# SMPS.net
KiCad netlist of a schematic drawn in Altium Designer
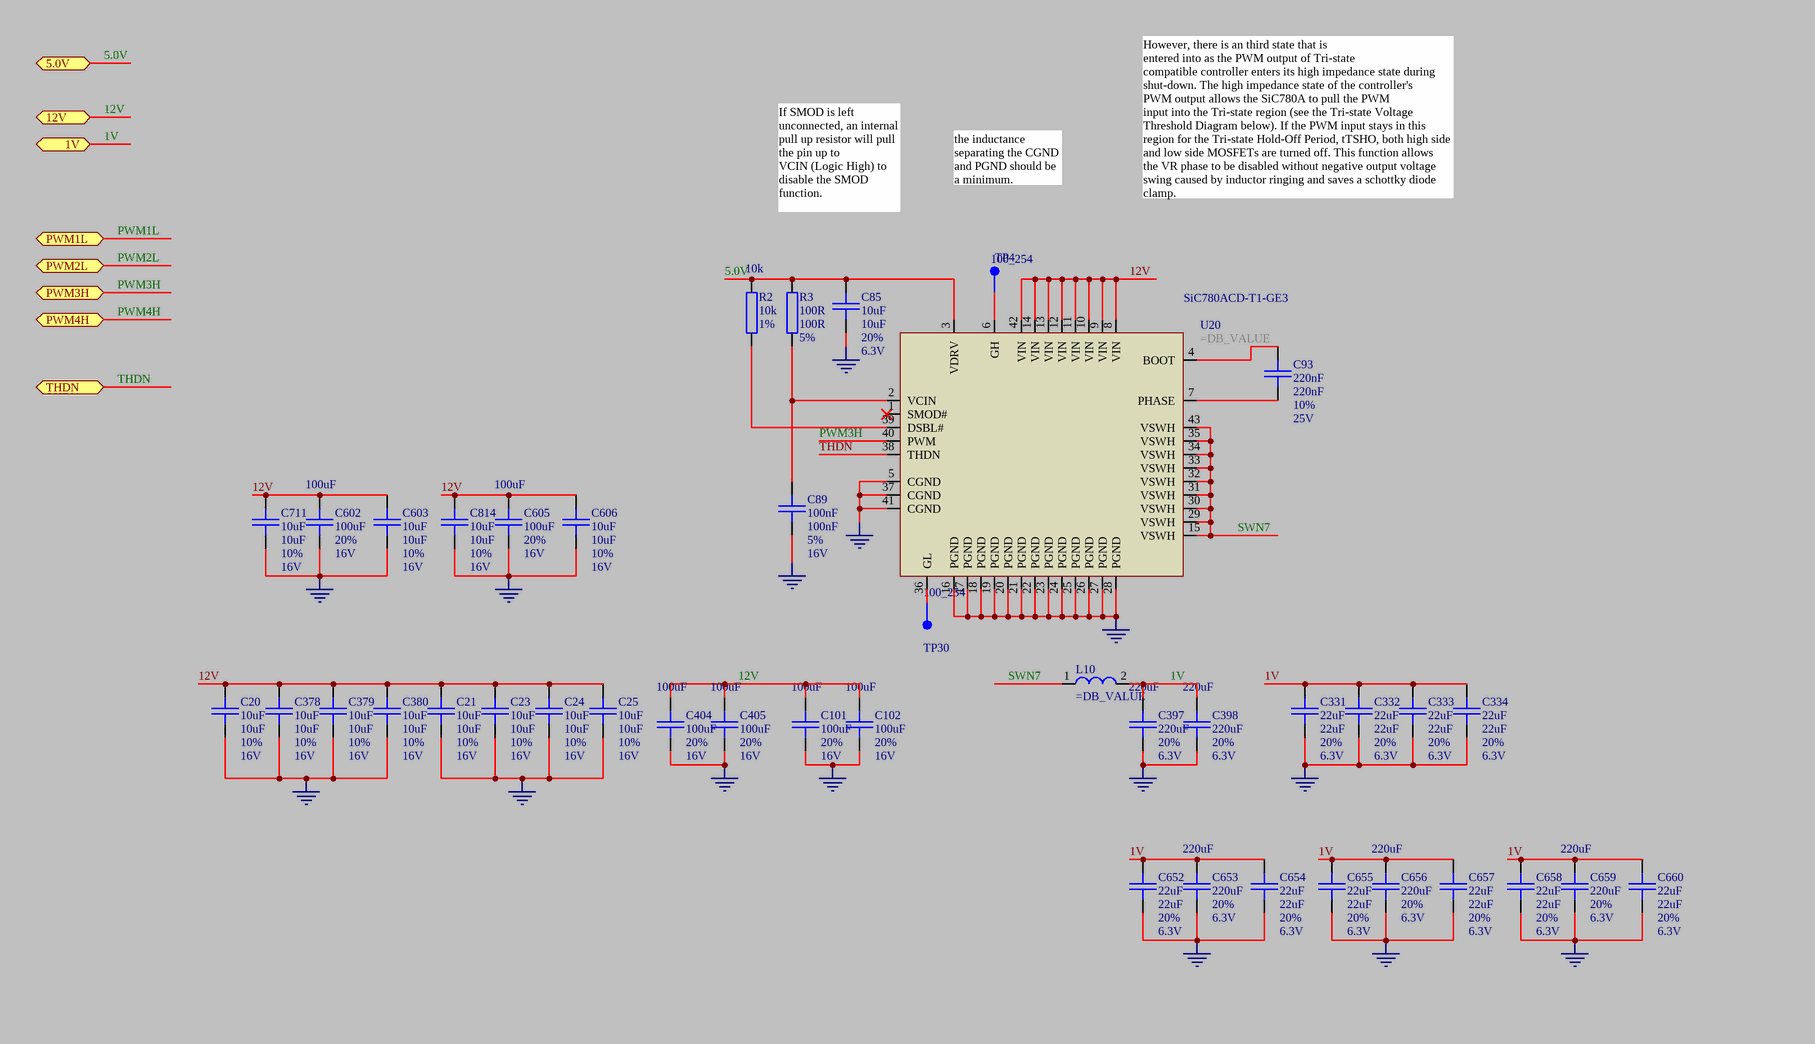
[diagram p0: SMPS.SchDoc, top left]
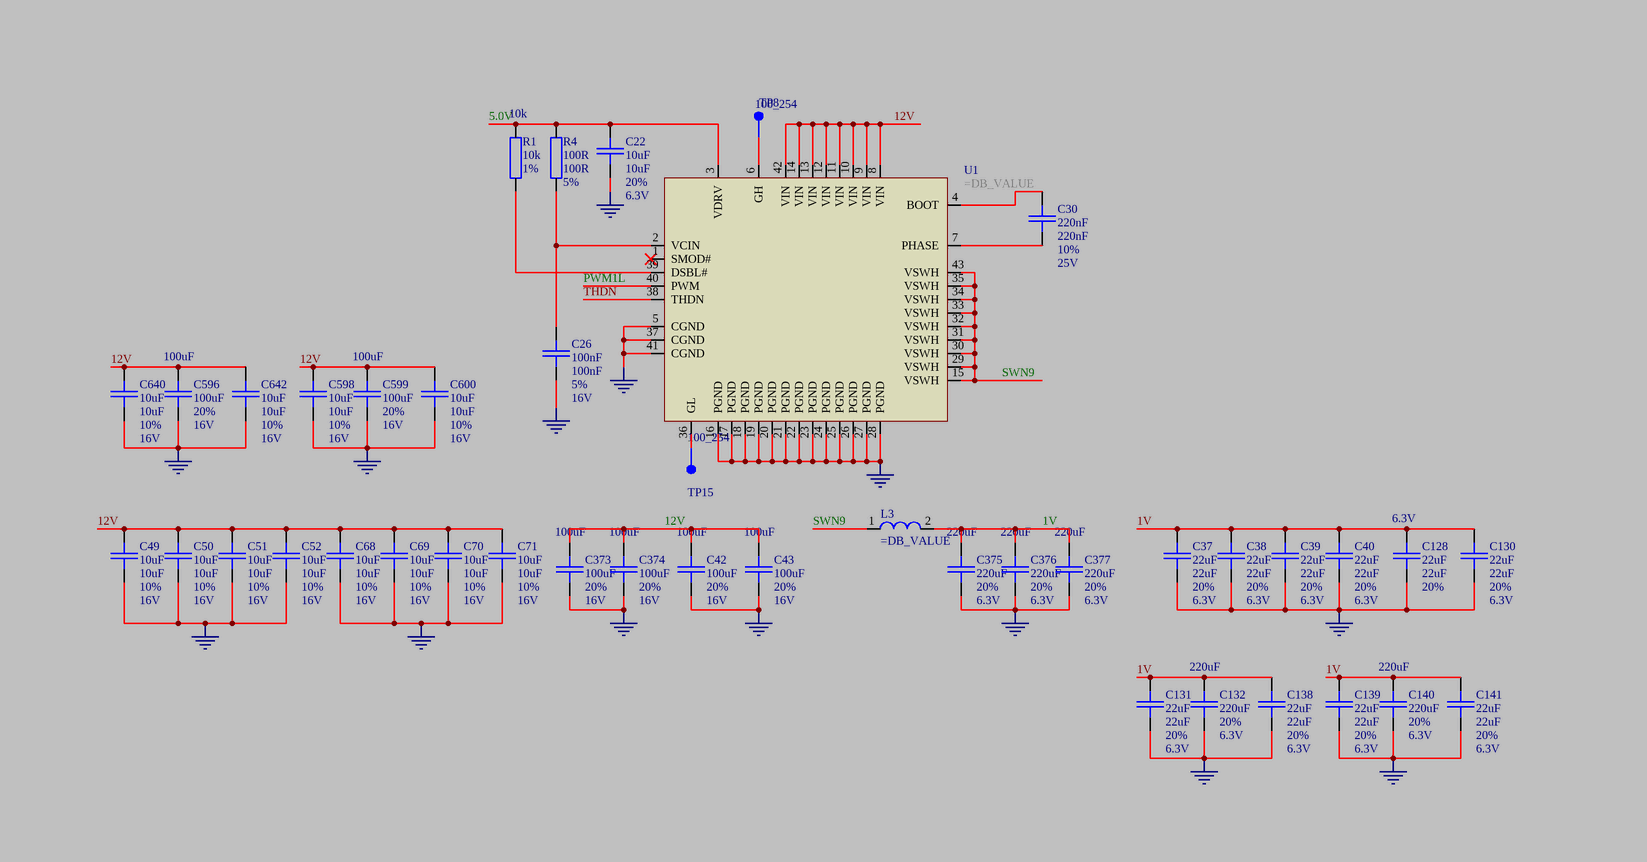
[diagram p1: SMPS.SchDoc, top right]
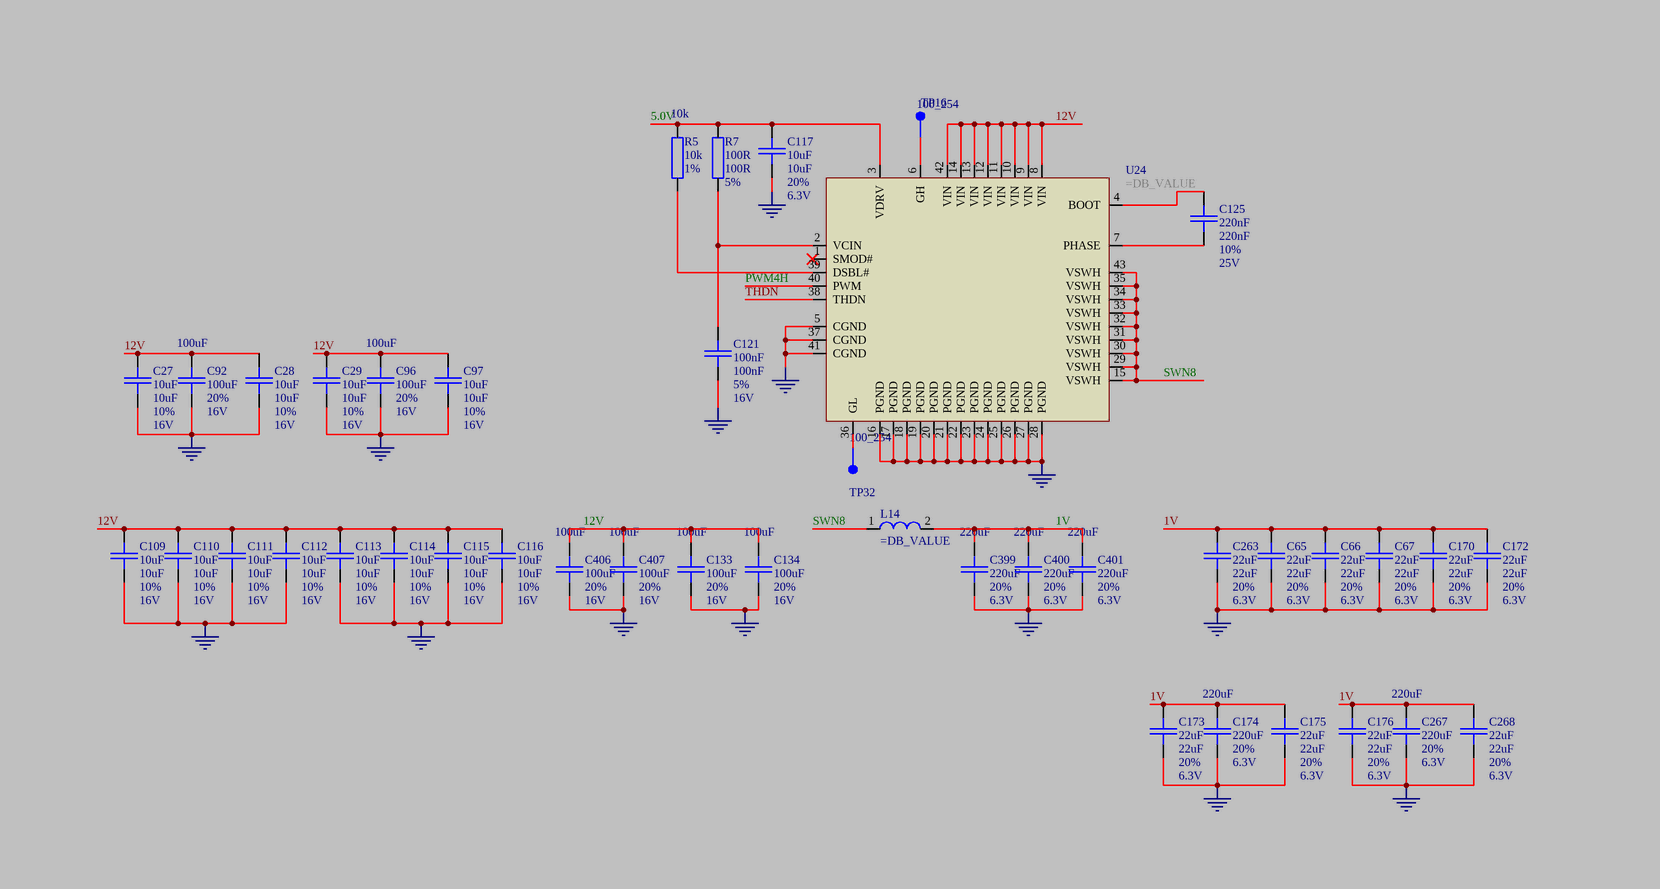
[diagram p2: SMPS.SchDoc, bottom left]
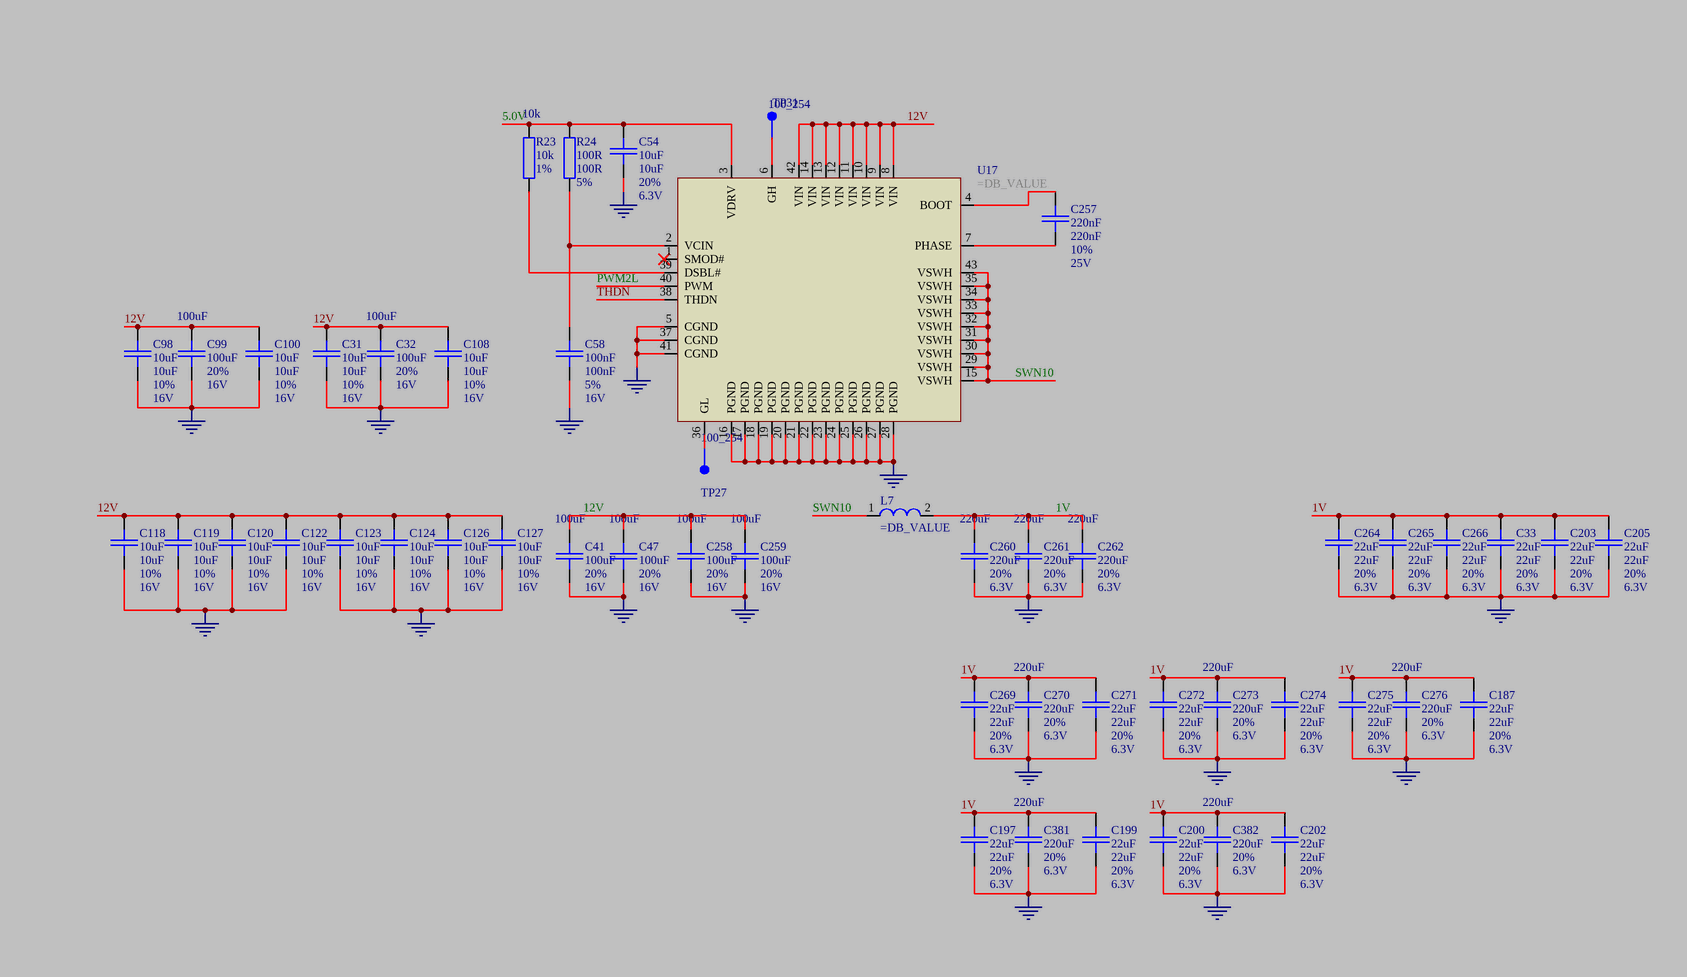
[diagram p3: SMPS.SchDoc, bottom right]

(export (version "E")
  (design (tool "Eeschema 10.0.6"))
  (components
    (comp (ref "C20")
      (value "10uF")
      (footprint "SMD_0805_CAPC2012X145N")
      (fields
        (field (name "DB_PART_NUMBER") "CAP000043636")
        (field (name "DB_VALUE") "10uF")
        (field (name "DB_TOLERANCE") "10%")
        (field (name "DB_VOLTAGE") "16V")
        (field (name "DB_MANUFACTURER_PART") "KEMET    C0805C106K4PAC")
        (field (name "DB_APPROVED_BY") "ISHIDDEN=T")
      )
      (libsource (lib "Database_Libs1") (part "C"))
    )
    (comp (ref "C21")
      (value "10uF")
      (footprint "SMD_0805_CAPC2012X145N")
      (fields
        (field (name "DB_PART_NUMBER") "CAP000043636")
        (field (name "DB_VALUE") "10uF")
        (field (name "DB_TOLERANCE") "10%")
        (field (name "DB_VOLTAGE") "16V")
        (field (name "DB_MANUFACTURER_PART") "KEMET    C0805C106K4PAC")
        (field (name "DB_APPROVED_BY") "ISHIDDEN=T")
      )
      (libsource (lib "Database_Libs1") (part "C"))
    )
    (comp (ref "C22")
      (value "10uF")
      (footprint "SMD_0603_CAPC1608X95N")
      (fields
        (field (name "DB_PART_NUMBER") "CAP000043646")
        (field (name "DB_VALUE") "10uF")
        (field (name "DB_TOLERANCE") "20%")
        (field (name "DB_VOLTAGE") "6.3V")
        (field (name "DB_MANUFACTURER_PART") "KEMET    C0603C106M9PAC")
        (field (name "DB_APPROVED_BY") "ISHIDDEN=T")
      )
      (libsource (lib "Database_Libs1") (part "C"))
    )
    (comp (ref "C23")
      (value "10uF")
      (footprint "SMD_0805_CAPC2012X145N")
      (fields
        (field (name "DB_PART_NUMBER") "CAP000043636")
        (field (name "DB_VALUE") "10uF")
        (field (name "DB_TOLERANCE") "10%")
        (field (name "DB_VOLTAGE") "16V")
        (field (name "DB_MANUFACTURER_PART") "KEMET    C0805C106K4PAC")
        (field (name "DB_APPROVED_BY") "ISHIDDEN=T")
      )
      (libsource (lib "Database_Libs1") (part "C"))
    )
    (comp (ref "C24")
      (value "10uF")
      (footprint "SMD_0805_CAPC2012X145N")
      (fields
        (field (name "DB_PART_NUMBER") "CAP000043636")
        (field (name "DB_VALUE") "10uF")
        (field (name "DB_TOLERANCE") "10%")
        (field (name "DB_VOLTAGE") "16V")
        (field (name "DB_MANUFACTURER_PART") "KEMET    C0805C106K4PAC")
        (field (name "DB_APPROVED_BY") "ISHIDDEN=T")
      )
      (libsource (lib "Database_Libs1") (part "C"))
    )
    (comp (ref "C25")
      (value "10uF")
      (footprint "SMD_0805_CAPC2012X145N")
      (fields
        (field (name "DB_PART_NUMBER") "CAP000043636")
        (field (name "DB_VALUE") "10uF")
        (field (name "DB_TOLERANCE") "10%")
        (field (name "DB_VOLTAGE") "16V")
        (field (name "DB_MANUFACTURER_PART") "KEMET    C0805C106K4PAC")
        (field (name "DB_APPROVED_BY") "ISHIDDEN=T")
      )
      (libsource (lib "Database_Libs1") (part "C"))
    )
    (comp (ref "C26")
      (value "100nF")
      (footprint "SMD_0603_CAPC1608X95N")
      (fields
        (field (name "DB_PART_NUMBER") "CAP000022706")
        (field (name "DB_VALUE") "100nF")
        (field (name "DB_TOLERANCE") "5%")
        (field (name "DB_VOLTAGE") "16V")
        (field (name "DB_MANUFACTURER_PART") "KEMET    C0603F104J4RAC")
        (field (name "DB_APPROVED_BY") "ISHIDDEN=T")
      )
      (libsource (lib "Database_Libs1") (part "C"))
    )
    (comp (ref "C27")
      (value "10uF")
      (footprint "SMD_0805_CAPC2012X145N")
      (fields
        (field (name "DB_PART_NUMBER") "CAP000043636")
        (field (name "DB_VALUE") "10uF")
        (field (name "DB_TOLERANCE") "10%")
        (field (name "DB_VOLTAGE") "16V")
        (field (name "DB_MANUFACTURER_PART") "KEMET    C0805C106K4PAC")
        (field (name "DB_APPROVED_BY") "ISHIDDEN=T")
      )
      (libsource (lib "Database_Libs1") (part "C"))
    )
    (comp (ref "C28")
      (value "10uF")
      (footprint "SMD_0805_CAPC2012X145N")
      (fields
        (field (name "DB_PART_NUMBER") "CAP000043636")
        (field (name "DB_VALUE") "10uF")
        (field (name "DB_TOLERANCE") "10%")
        (field (name "DB_VOLTAGE") "16V")
        (field (name "DB_MANUFACTURER_PART") "KEMET    C0805C106K4PAC")
        (field (name "DB_APPROVED_BY") "ISHIDDEN=T")
      )
      (libsource (lib "Database_Libs1") (part "C"))
    )
    (comp (ref "C29")
      (value "10uF")
      (footprint "SMD_0805_CAPC2012X145N")
      (fields
        (field (name "DB_PART_NUMBER") "CAP000043636")
        (field (name "DB_VALUE") "10uF")
        (field (name "DB_TOLERANCE") "10%")
        (field (name "DB_VOLTAGE") "16V")
        (field (name "DB_MANUFACTURER_PART") "KEMET    C0805C106K4PAC")
        (field (name "DB_APPROVED_BY") "ISHIDDEN=T")
      )
      (libsource (lib "Database_Libs1") (part "C"))
    )
    (comp (ref "C30")
      (value "220nF")
      (footprint "SMD_0603_CAPC1608X95N")
      (fields
        (field (name "DB_PART_NUMBER") "CAP000022968")
        (field (name "DB_VALUE") "220nF")
        (field (name "DB_TOLERANCE") "10%")
        (field (name "DB_VOLTAGE") "25V")
        (field (name "DB_MANUFACTURER_PART") "KEMET    C0603F224K3RAC")
        (field (name "DB_APPROVED_BY") "ISHIDDEN=T")
      )
      (libsource (lib "Database_Libs1") (part "C"))
    )
    (comp (ref "C31")
      (value "10uF")
      (footprint "SMD_0805_CAPC2012X145N")
      (fields
        (field (name "DB_PART_NUMBER") "CAP000043636")
        (field (name "DB_VALUE") "10uF")
        (field (name "DB_TOLERANCE") "10%")
        (field (name "DB_VOLTAGE") "16V")
        (field (name "DB_MANUFACTURER_PART") "KEMET    C0805C106K4PAC")
        (field (name "DB_APPROVED_BY") "ISHIDDEN=T")
      )
      (libsource (lib "Database_Libs1") (part "C"))
    )
    (comp (ref "C32")
      (value "100uF")
      (footprint "SMD_1210_CAPC3225X270N")
      (fields
        (field (name "DB_PART_NUMBER") "TMP-2512")
        (field (name "DB_VALUE") "100uF")
        (field (name "DB_TOLERANCE") "20%")
        (field (name "DB_VOLTAGE") "16V")
        (field (name "DB_MANUFACTURER_PART") "YAGEO    CC1210MRX5R7BB107")
      )
      (libsource (lib "Database_Libs1") (part "C"))
    )
    (comp (ref "C33")
      (value "22uF")
      (footprint "SMD_0805_CAPC2012X145N")
      (fields
        (field (name "DB_PART_NUMBER") "CAP000043686")
        (field (name "DB_VALUE") "22uF")
        (field (name "DB_TOLERANCE") "20%")
        (field (name "DB_VOLTAGE") "6.3V")
        (field (name "DB_MANUFACTURER_PART") "KEMET    C0805C226M9PAC")
        (field (name "DB_APPROVED_BY") "ISHIDDEN=T")
      )
      (libsource (lib "Database_Libs1") (part "C"))
    )
    (comp (ref "C37")
      (value "22uF")
      (footprint "SMD_0805_CAPC2012X145N")
      (fields
        (field (name "DB_PART_NUMBER") "CAP000043686")
        (field (name "DB_VALUE") "22uF")
        (field (name "DB_TOLERANCE") "20%")
        (field (name "DB_VOLTAGE") "6.3V")
        (field (name "DB_MANUFACTURER_PART") "KEMET    C0805C226M9PAC")
        (field (name "DB_APPROVED_BY") "ISHIDDEN=T")
      )
      (libsource (lib "Database_Libs1") (part "C"))
    )
    (comp (ref "C38")
      (value "22uF")
      (footprint "SMD_0805_CAPC2012X145N")
      (fields
        (field (name "DB_PART_NUMBER") "CAP000043686")
        (field (name "DB_VALUE") "22uF")
        (field (name "DB_TOLERANCE") "20%")
        (field (name "DB_VOLTAGE") "6.3V")
        (field (name "DB_MANUFACTURER_PART") "KEMET    C0805C226M9PAC")
        (field (name "DB_APPROVED_BY") "ISHIDDEN=T")
      )
      (libsource (lib "Database_Libs1") (part "C"))
    )
    (comp (ref "C39")
      (value "22uF")
      (footprint "SMD_0805_CAPC2012X145N")
      (fields
        (field (name "DB_PART_NUMBER") "CAP000043686")
        (field (name "DB_VALUE") "22uF")
        (field (name "DB_TOLERANCE") "20%")
        (field (name "DB_VOLTAGE") "6.3V")
        (field (name "DB_MANUFACTURER_PART") "KEMET    C0805C226M9PAC")
        (field (name "DB_APPROVED_BY") "ISHIDDEN=T")
      )
      (libsource (lib "Database_Libs1") (part "C"))
    )
    (comp (ref "C40")
      (value "22uF")
      (footprint "SMD_0805_CAPC2012X145N")
      (fields
        (field (name "DB_PART_NUMBER") "CAP000043686")
        (field (name "DB_VALUE") "22uF")
        (field (name "DB_TOLERANCE") "20%")
        (field (name "DB_VOLTAGE") "6.3V")
        (field (name "DB_MANUFACTURER_PART") "KEMET    C0805C226M9PAC")
        (field (name "DB_APPROVED_BY") "ISHIDDEN=T")
      )
      (libsource (lib "Database_Libs1") (part "C"))
    )
    (comp (ref "C41")
      (value "100uF")
      (footprint "SMD_1210_CAPC3225X270N")
      (fields
        (field (name "DB_PART_NUMBER") "TMP-2512")
        (field (name "DB_VALUE") "100uF")
        (field (name "DB_TOLERANCE") "20%")
        (field (name "DB_VOLTAGE") "16V")
        (field (name "DB_MANUFACTURER_PART") "YAGEO    CC1210MRX5R7BB107")
      )
      (libsource (lib "Database_Libs1") (part "C"))
    )
    (comp (ref "C42")
      (value "100uF")
      (footprint "SMD_1210_CAPC3225X270N")
      (fields
        (field (name "DB_PART_NUMBER") "TMP-2512")
        (field (name "DB_VALUE") "100uF")
        (field (name "DB_TOLERANCE") "20%")
        (field (name "DB_VOLTAGE") "16V")
        (field (name "DB_MANUFACTURER_PART") "YAGEO    CC1210MRX5R7BB107")
      )
      (libsource (lib "Database_Libs1") (part "C"))
    )
    (comp (ref "C43")
      (value "100uF")
      (footprint "SMD_1210_CAPC3225X270N")
      (fields
        (field (name "DB_PART_NUMBER") "TMP-2512")
        (field (name "DB_VALUE") "100uF")
        (field (name "DB_TOLERANCE") "20%")
        (field (name "DB_VOLTAGE") "16V")
        (field (name "DB_MANUFACTURER_PART") "YAGEO    CC1210MRX5R7BB107")
      )
      (libsource (lib "Database_Libs1") (part "C"))
    )
    (comp (ref "C47")
      (value "100uF")
      (footprint "SMD_1210_CAPC3225X270N")
      (fields
        (field (name "DB_PART_NUMBER") "TMP-2512")
        (field (name "DB_VALUE") "100uF")
        (field (name "DB_TOLERANCE") "20%")
        (field (name "DB_VOLTAGE") "16V")
        (field (name "DB_MANUFACTURER_PART") "YAGEO    CC1210MRX5R7BB107")
      )
      (libsource (lib "Database_Libs1") (part "C"))
    )
    (comp (ref "C49")
      (value "10uF")
      (footprint "SMD_0805_CAPC2012X145N")
      (fields
        (field (name "DB_PART_NUMBER") "CAP000043636")
        (field (name "DB_VALUE") "10uF")
        (field (name "DB_TOLERANCE") "10%")
        (field (name "DB_VOLTAGE") "16V")
        (field (name "DB_MANUFACTURER_PART") "KEMET    C0805C106K4PAC")
        (field (name "DB_APPROVED_BY") "ISHIDDEN=T")
      )
      (libsource (lib "Database_Libs1") (part "C"))
    )
    (comp (ref "C50")
      (value "10uF")
      (footprint "SMD_0805_CAPC2012X145N")
      (fields
        (field (name "DB_PART_NUMBER") "CAP000043636")
        (field (name "DB_VALUE") "10uF")
        (field (name "DB_TOLERANCE") "10%")
        (field (name "DB_VOLTAGE") "16V")
        (field (name "DB_MANUFACTURER_PART") "KEMET    C0805C106K4PAC")
        (field (name "DB_APPROVED_BY") "ISHIDDEN=T")
      )
      (libsource (lib "Database_Libs1") (part "C"))
    )
    (comp (ref "C51")
      (value "10uF")
      (footprint "SMD_0805_CAPC2012X145N")
      (fields
        (field (name "DB_PART_NUMBER") "CAP000043636")
        (field (name "DB_VALUE") "10uF")
        (field (name "DB_TOLERANCE") "10%")
        (field (name "DB_VOLTAGE") "16V")
        (field (name "DB_MANUFACTURER_PART") "KEMET    C0805C106K4PAC")
        (field (name "DB_APPROVED_BY") "ISHIDDEN=T")
      )
      (libsource (lib "Database_Libs1") (part "C"))
    )
    (comp (ref "C52")
      (value "10uF")
      (footprint "SMD_0805_CAPC2012X145N")
      (fields
        (field (name "DB_PART_NUMBER") "CAP000043636")
        (field (name "DB_VALUE") "10uF")
        (field (name "DB_TOLERANCE") "10%")
        (field (name "DB_VOLTAGE") "16V")
        (field (name "DB_MANUFACTURER_PART") "KEMET    C0805C106K4PAC")
        (field (name "DB_APPROVED_BY") "ISHIDDEN=T")
      )
      (libsource (lib "Database_Libs1") (part "C"))
    )
    (comp (ref "C54")
      (value "10uF")
      (footprint "SMD_0603_CAPC1608X95N")
      (fields
        (field (name "DB_PART_NUMBER") "CAP000043646")
        (field (name "DB_VALUE") "10uF")
        (field (name "DB_TOLERANCE") "20%")
        (field (name "DB_VOLTAGE") "6.3V")
        (field (name "DB_MANUFACTURER_PART") "KEMET    C0603C106M9PAC")
        (field (name "DB_APPROVED_BY") "ISHIDDEN=T")
      )
      (libsource (lib "Database_Libs1") (part "C"))
    )
    (comp (ref "C58")
      (value "100nF")
      (footprint "SMD_0603_CAPC1608X95N")
      (fields
        (field (name "DB_PART_NUMBER") "CAP000022706")
        (field (name "DB_VALUE") "100nF")
        (field (name "DB_TOLERANCE") "5%")
        (field (name "DB_VOLTAGE") "16V")
        (field (name "DB_MANUFACTURER_PART") "KEMET    C0603F104J4RAC")
        (field (name "DB_APPROVED_BY") "ISHIDDEN=T")
      )
      (libsource (lib "Database_Libs1") (part "C"))
    )
    (comp (ref "C65")
      (value "22uF")
      (footprint "SMD_0805_CAPC2012X145N")
      (fields
        (field (name "DB_PART_NUMBER") "CAP000043686")
        (field (name "DB_VALUE") "22uF")
        (field (name "DB_TOLERANCE") "20%")
        (field (name "DB_VOLTAGE") "6.3V")
        (field (name "DB_MANUFACTURER_PART") "KEMET    C0805C226M9PAC")
        (field (name "DB_APPROVED_BY") "ISHIDDEN=T")
      )
      (libsource (lib "Database_Libs1") (part "C"))
    )
    (comp (ref "C66")
      (value "22uF")
      (footprint "SMD_0805_CAPC2012X145N")
      (fields
        (field (name "DB_PART_NUMBER") "CAP000043686")
        (field (name "DB_VALUE") "22uF")
        (field (name "DB_TOLERANCE") "20%")
        (field (name "DB_VOLTAGE") "6.3V")
        (field (name "DB_MANUFACTURER_PART") "KEMET    C0805C226M9PAC")
        (field (name "DB_APPROVED_BY") "ISHIDDEN=T")
      )
      (libsource (lib "Database_Libs1") (part "C"))
    )
    (comp (ref "C67")
      (value "22uF")
      (footprint "SMD_0805_CAPC2012X145N")
      (fields
        (field (name "DB_PART_NUMBER") "CAP000043686")
        (field (name "DB_VALUE") "22uF")
        (field (name "DB_TOLERANCE") "20%")
        (field (name "DB_VOLTAGE") "6.3V")
        (field (name "DB_MANUFACTURER_PART") "KEMET    C0805C226M9PAC")
        (field (name "DB_APPROVED_BY") "ISHIDDEN=T")
      )
      (libsource (lib "Database_Libs1") (part "C"))
    )
    (comp (ref "C68")
      (value "10uF")
      (footprint "SMD_0805_CAPC2012X145N")
      (fields
        (field (name "DB_PART_NUMBER") "CAP000043636")
        (field (name "DB_VALUE") "10uF")
        (field (name "DB_TOLERANCE") "10%")
        (field (name "DB_VOLTAGE") "16V")
        (field (name "DB_MANUFACTURER_PART") "KEMET    C0805C106K4PAC")
        (field (name "DB_APPROVED_BY") "ISHIDDEN=T")
      )
      (libsource (lib "Database_Libs1") (part "C"))
    )
    (comp (ref "C69")
      (value "10uF")
      (footprint "SMD_0805_CAPC2012X145N")
      (fields
        (field (name "DB_PART_NUMBER") "CAP000043636")
        (field (name "DB_VALUE") "10uF")
        (field (name "DB_TOLERANCE") "10%")
        (field (name "DB_VOLTAGE") "16V")
        (field (name "DB_MANUFACTURER_PART") "KEMET    C0805C106K4PAC")
        (field (name "DB_APPROVED_BY") "ISHIDDEN=T")
      )
      (libsource (lib "Database_Libs1") (part "C"))
    )
    (comp (ref "C70")
      (value "10uF")
      (footprint "SMD_0805_CAPC2012X145N")
      (fields
        (field (name "DB_PART_NUMBER") "CAP000043636")
        (field (name "DB_VALUE") "10uF")
        (field (name "DB_TOLERANCE") "10%")
        (field (name "DB_VOLTAGE") "16V")
        (field (name "DB_MANUFACTURER_PART") "KEMET    C0805C106K4PAC")
        (field (name "DB_APPROVED_BY") "ISHIDDEN=T")
      )
      (libsource (lib "Database_Libs1") (part "C"))
    )
    (comp (ref "C71")
      (value "10uF")
      (footprint "SMD_0805_CAPC2012X145N")
      (fields
        (field (name "DB_PART_NUMBER") "CAP000043636")
        (field (name "DB_VALUE") "10uF")
        (field (name "DB_TOLERANCE") "10%")
        (field (name "DB_VOLTAGE") "16V")
        (field (name "DB_MANUFACTURER_PART") "KEMET    C0805C106K4PAC")
        (field (name "DB_APPROVED_BY") "ISHIDDEN=T")
      )
      (libsource (lib "Database_Libs1") (part "C"))
    )
    (comp (ref "C85")
      (value "10uF")
      (footprint "SMD_0603_CAPC1608X95N")
      (fields
        (field (name "DB_PART_NUMBER") "CAP000043646")
        (field (name "DB_VALUE") "10uF")
        (field (name "DB_TOLERANCE") "20%")
        (field (name "DB_VOLTAGE") "6.3V")
        (field (name "DB_MANUFACTURER_PART") "KEMET    C0603C106M9PAC")
        (field (name "DB_APPROVED_BY") "ISHIDDEN=T")
      )
      (libsource (lib "Database_Libs1") (part "C"))
    )
    (comp (ref "C89")
      (value "100nF")
      (footprint "SMD_0603_CAPC1608X95N")
      (fields
        (field (name "DB_PART_NUMBER") "CAP000022706")
        (field (name "DB_VALUE") "100nF")
        (field (name "DB_TOLERANCE") "5%")
        (field (name "DB_VOLTAGE") "16V")
        (field (name "DB_MANUFACTURER_PART") "KEMET    C0603F104J4RAC")
        (field (name "DB_APPROVED_BY") "ISHIDDEN=T")
      )
      (libsource (lib "Database_Libs1") (part "C"))
    )
    (comp (ref "C92")
      (value "100uF")
      (footprint "SMD_1210_CAPC3225X270N")
      (fields
        (field (name "DB_PART_NUMBER") "TMP-2512")
        (field (name "DB_VALUE") "100uF")
        (field (name "DB_TOLERANCE") "20%")
        (field (name "DB_VOLTAGE") "16V")
        (field (name "DB_MANUFACTURER_PART") "YAGEO    CC1210MRX5R7BB107")
      )
      (libsource (lib "Database_Libs1") (part "C"))
    )
    (comp (ref "C93")
      (value "220nF")
      (footprint "SMD_0603_CAPC1608X95N")
      (fields
        (field (name "DB_PART_NUMBER") "CAP000022968")
        (field (name "DB_VALUE") "220nF")
        (field (name "DB_TOLERANCE") "10%")
        (field (name "DB_VOLTAGE") "25V")
        (field (name "DB_MANUFACTURER_PART") "KEMET    C0603F224K3RAC")
        (field (name "DB_APPROVED_BY") "ISHIDDEN=T")
      )
      (libsource (lib "Database_Libs1") (part "C"))
    )
    (comp (ref "C96")
      (value "100uF")
      (footprint "SMD_1210_CAPC3225X270N")
      (fields
        (field (name "DB_PART_NUMBER") "TMP-2512")
        (field (name "DB_VALUE") "100uF")
        (field (name "DB_TOLERANCE") "20%")
        (field (name "DB_VOLTAGE") "16V")
        (field (name "DB_MANUFACTURER_PART") "YAGEO    CC1210MRX5R7BB107")
      )
      (libsource (lib "Database_Libs1") (part "C"))
    )
    (comp (ref "C97")
      (value "10uF")
      (footprint "SMD_0805_CAPC2012X145N")
      (fields
        (field (name "DB_PART_NUMBER") "CAP000043636")
        (field (name "DB_VALUE") "10uF")
        (field (name "DB_TOLERANCE") "10%")
        (field (name "DB_VOLTAGE") "16V")
        (field (name "DB_MANUFACTURER_PART") "KEMET    C0805C106K4PAC")
        (field (name "DB_APPROVED_BY") "ISHIDDEN=T")
      )
      (libsource (lib "Database_Libs1") (part "C"))
    )
    (comp (ref "C98")
      (value "10uF")
      (footprint "SMD_0805_CAPC2012X145N")
      (fields
        (field (name "DB_PART_NUMBER") "CAP000043636")
        (field (name "DB_VALUE") "10uF")
        (field (name "DB_TOLERANCE") "10%")
        (field (name "DB_VOLTAGE") "16V")
        (field (name "DB_MANUFACTURER_PART") "KEMET    C0805C106K4PAC")
        (field (name "DB_APPROVED_BY") "ISHIDDEN=T")
      )
      (libsource (lib "Database_Libs1") (part "C"))
    )
    (comp (ref "C99")
      (value "100uF")
      (footprint "SMD_1210_CAPC3225X270N")
      (fields
        (field (name "DB_PART_NUMBER") "TMP-2512")
        (field (name "DB_VALUE") "100uF")
        (field (name "DB_TOLERANCE") "20%")
        (field (name "DB_VOLTAGE") "16V")
        (field (name "DB_MANUFACTURER_PART") "YAGEO    CC1210MRX5R7BB107")
      )
      (libsource (lib "Database_Libs1") (part "C"))
    )
    (comp (ref "C100")
      (value "10uF")
      (footprint "SMD_0805_CAPC2012X145N")
      (fields
        (field (name "DB_PART_NUMBER") "CAP000043636")
        (field (name "DB_VALUE") "10uF")
        (field (name "DB_TOLERANCE") "10%")
        (field (name "DB_VOLTAGE") "16V")
        (field (name "DB_MANUFACTURER_PART") "KEMET    C0805C106K4PAC")
        (field (name "DB_APPROVED_BY") "ISHIDDEN=T")
      )
      (libsource (lib "Database_Libs1") (part "C"))
    )
    (comp (ref "C101")
      (value "100uF")
      (footprint "SMD_1210_CAPC3225X270N")
      (fields
        (field (name "DB_PART_NUMBER") "TMP-2512")
        (field (name "DB_VALUE") "100uF")
        (field (name "DB_TOLERANCE") "20%")
        (field (name "DB_VOLTAGE") "16V")
        (field (name "DB_MANUFACTURER_PART") "YAGEO    CC1210MRX5R7BB107")
      )
      (libsource (lib "Database_Libs1") (part "C"))
    )
    (comp (ref "C102")
      (value "100uF")
      (footprint "SMD_1210_CAPC3225X270N")
      (fields
        (field (name "DB_PART_NUMBER") "TMP-2512")
        (field (name "DB_VALUE") "100uF")
        (field (name "DB_TOLERANCE") "20%")
        (field (name "DB_VOLTAGE") "16V")
        (field (name "DB_MANUFACTURER_PART") "YAGEO    CC1210MRX5R7BB107")
      )
      (libsource (lib "Database_Libs1") (part "C"))
    )
    (comp (ref "C108")
      (value "10uF")
      (footprint "SMD_0805_CAPC2012X145N")
      (fields
        (field (name "DB_PART_NUMBER") "CAP000043636")
        (field (name "DB_VALUE") "10uF")
        (field (name "DB_TOLERANCE") "10%")
        (field (name "DB_VOLTAGE") "16V")
        (field (name "DB_MANUFACTURER_PART") "KEMET    C0805C106K4PAC")
        (field (name "DB_APPROVED_BY") "ISHIDDEN=T")
      )
      (libsource (lib "Database_Libs1") (part "C"))
    )
    (comp (ref "C109")
      (value "10uF")
      (footprint "SMD_0805_CAPC2012X145N")
      (fields
        (field (name "DB_PART_NUMBER") "CAP000043636")
        (field (name "DB_VALUE") "10uF")
        (field (name "DB_TOLERANCE") "10%")
        (field (name "DB_VOLTAGE") "16V")
        (field (name "DB_MANUFACTURER_PART") "KEMET    C0805C106K4PAC")
        (field (name "DB_APPROVED_BY") "ISHIDDEN=T")
      )
      (libsource (lib "Database_Libs1") (part "C"))
    )
    (comp (ref "C110")
      (value "10uF")
      (footprint "SMD_0805_CAPC2012X145N")
      (fields
        (field (name "DB_PART_NUMBER") "CAP000043636")
        (field (name "DB_VALUE") "10uF")
        (field (name "DB_TOLERANCE") "10%")
        (field (name "DB_VOLTAGE") "16V")
        (field (name "DB_MANUFACTURER_PART") "KEMET    C0805C106K4PAC")
        (field (name "DB_APPROVED_BY") "ISHIDDEN=T")
      )
      (libsource (lib "Database_Libs1") (part "C"))
    )
    (comp (ref "C111")
      (value "10uF")
      (footprint "SMD_0805_CAPC2012X145N")
      (fields
        (field (name "DB_PART_NUMBER") "CAP000043636")
        (field (name "DB_VALUE") "10uF")
        (field (name "DB_TOLERANCE") "10%")
        (field (name "DB_VOLTAGE") "16V")
        (field (name "DB_MANUFACTURER_PART") "KEMET    C0805C106K4PAC")
        (field (name "DB_APPROVED_BY") "ISHIDDEN=T")
      )
      (libsource (lib "Database_Libs1") (part "C"))
    )
    (comp (ref "C112")
      (value "10uF")
      (footprint "SMD_0805_CAPC2012X145N")
      (fields
        (field (name "DB_PART_NUMBER") "CAP000043636")
        (field (name "DB_VALUE") "10uF")
        (field (name "DB_TOLERANCE") "10%")
        (field (name "DB_VOLTAGE") "16V")
        (field (name "DB_MANUFACTURER_PART") "KEMET    C0805C106K4PAC")
        (field (name "DB_APPROVED_BY") "ISHIDDEN=T")
      )
      (libsource (lib "Database_Libs1") (part "C"))
    )
    (comp (ref "C113")
      (value "10uF")
      (footprint "SMD_0805_CAPC2012X145N")
      (fields
        (field (name "DB_PART_NUMBER") "CAP000043636")
        (field (name "DB_VALUE") "10uF")
        (field (name "DB_TOLERANCE") "10%")
        (field (name "DB_VOLTAGE") "16V")
        (field (name "DB_MANUFACTURER_PART") "KEMET    C0805C106K4PAC")
        (field (name "DB_APPROVED_BY") "ISHIDDEN=T")
      )
      (libsource (lib "Database_Libs1") (part "C"))
    )
    (comp (ref "C114")
      (value "10uF")
      (footprint "SMD_0805_CAPC2012X145N")
      (fields
        (field (name "DB_PART_NUMBER") "CAP000043636")
        (field (name "DB_VALUE") "10uF")
        (field (name "DB_TOLERANCE") "10%")
        (field (name "DB_VOLTAGE") "16V")
        (field (name "DB_MANUFACTURER_PART") "KEMET    C0805C106K4PAC")
        (field (name "DB_APPROVED_BY") "ISHIDDEN=T")
      )
      (libsource (lib "Database_Libs1") (part "C"))
    )
    (comp (ref "C115")
      (value "10uF")
      (footprint "SMD_0805_CAPC2012X145N")
      (fields
        (field (name "DB_PART_NUMBER") "CAP000043636")
        (field (name "DB_VALUE") "10uF")
        (field (name "DB_TOLERANCE") "10%")
        (field (name "DB_VOLTAGE") "16V")
        (field (name "DB_MANUFACTURER_PART") "KEMET    C0805C106K4PAC")
        (field (name "DB_APPROVED_BY") "ISHIDDEN=T")
      )
      (libsource (lib "Database_Libs1") (part "C"))
    )
    (comp (ref "C116")
      (value "10uF")
      (footprint "SMD_0805_CAPC2012X145N")
      (fields
        (field (name "DB_PART_NUMBER") "CAP000043636")
        (field (name "DB_VALUE") "10uF")
        (field (name "DB_TOLERANCE") "10%")
        (field (name "DB_VOLTAGE") "16V")
        (field (name "DB_MANUFACTURER_PART") "KEMET    C0805C106K4PAC")
        (field (name "DB_APPROVED_BY") "ISHIDDEN=T")
      )
      (libsource (lib "Database_Libs1") (part "C"))
    )
    (comp (ref "C117")
      (value "10uF")
      (footprint "SMD_0603_CAPC1608X95N")
      (fields
        (field (name "DB_PART_NUMBER") "CAP000043646")
        (field (name "DB_VALUE") "10uF")
        (field (name "DB_TOLERANCE") "20%")
        (field (name "DB_VOLTAGE") "6.3V")
        (field (name "DB_MANUFACTURER_PART") "KEMET    C0603C106M9PAC")
        (field (name "DB_APPROVED_BY") "ISHIDDEN=T")
      )
      (libsource (lib "Database_Libs1") (part "C"))
    )
    (comp (ref "C118")
      (value "10uF")
      (footprint "SMD_0805_CAPC2012X145N")
      (fields
        (field (name "DB_PART_NUMBER") "CAP000043636")
        (field (name "DB_VALUE") "10uF")
        (field (name "DB_TOLERANCE") "10%")
        (field (name "DB_VOLTAGE") "16V")
        (field (name "DB_MANUFACTURER_PART") "KEMET    C0805C106K4PAC")
        (field (name "DB_APPROVED_BY") "ISHIDDEN=T")
      )
      (libsource (lib "Database_Libs1") (part "C"))
    )
    (comp (ref "C119")
      (value "10uF")
      (footprint "SMD_0805_CAPC2012X145N")
      (fields
        (field (name "DB_PART_NUMBER") "CAP000043636")
        (field (name "DB_VALUE") "10uF")
        (field (name "DB_TOLERANCE") "10%")
        (field (name "DB_VOLTAGE") "16V")
        (field (name "DB_MANUFACTURER_PART") "KEMET    C0805C106K4PAC")
        (field (name "DB_APPROVED_BY") "ISHIDDEN=T")
      )
      (libsource (lib "Database_Libs1") (part "C"))
    )
    (comp (ref "C120")
      (value "10uF")
      (footprint "SMD_0805_CAPC2012X145N")
      (fields
        (field (name "DB_PART_NUMBER") "CAP000043636")
        (field (name "DB_VALUE") "10uF")
        (field (name "DB_TOLERANCE") "10%")
        (field (name "DB_VOLTAGE") "16V")
        (field (name "DB_MANUFACTURER_PART") "KEMET    C0805C106K4PAC")
        (field (name "DB_APPROVED_BY") "ISHIDDEN=T")
      )
      (libsource (lib "Database_Libs1") (part "C"))
    )
    (comp (ref "C121")
      (value "100nF")
      (footprint "SMD_0603_CAPC1608X95N")
      (fields
        (field (name "DB_PART_NUMBER") "CAP000022706")
        (field (name "DB_VALUE") "100nF")
        (field (name "DB_TOLERANCE") "5%")
        (field (name "DB_VOLTAGE") "16V")
        (field (name "DB_MANUFACTURER_PART") "KEMET    C0603F104J4RAC")
        (field (name "DB_APPROVED_BY") "ISHIDDEN=T")
      )
      (libsource (lib "Database_Libs1") (part "C"))
    )
    (comp (ref "C122")
      (value "10uF")
      (footprint "SMD_0805_CAPC2012X145N")
      (fields
        (field (name "DB_PART_NUMBER") "CAP000043636")
        (field (name "DB_VALUE") "10uF")
        (field (name "DB_TOLERANCE") "10%")
        (field (name "DB_VOLTAGE") "16V")
        (field (name "DB_MANUFACTURER_PART") "KEMET    C0805C106K4PAC")
        (field (name "DB_APPROVED_BY") "ISHIDDEN=T")
      )
      (libsource (lib "Database_Libs1") (part "C"))
    )
    (comp (ref "C123")
      (value "10uF")
      (footprint "SMD_0805_CAPC2012X145N")
      (fields
        (field (name "DB_PART_NUMBER") "CAP000043636")
        (field (name "DB_VALUE") "10uF")
        (field (name "DB_TOLERANCE") "10%")
        (field (name "DB_VOLTAGE") "16V")
        (field (name "DB_MANUFACTURER_PART") "KEMET    C0805C106K4PAC")
        (field (name "DB_APPROVED_BY") "ISHIDDEN=T")
      )
      (libsource (lib "Database_Libs1") (part "C"))
    )
    (comp (ref "C124")
      (value "10uF")
      (footprint "SMD_0805_CAPC2012X145N")
      (fields
        (field (name "DB_PART_NUMBER") "CAP000043636")
        (field (name "DB_VALUE") "10uF")
        (field (name "DB_TOLERANCE") "10%")
        (field (name "DB_VOLTAGE") "16V")
        (field (name "DB_MANUFACTURER_PART") "KEMET    C0805C106K4PAC")
        (field (name "DB_APPROVED_BY") "ISHIDDEN=T")
      )
      (libsource (lib "Database_Libs1") (part "C"))
    )
    (comp (ref "C125")
      (value "220nF")
      (footprint "SMD_0603_CAPC1608X95N")
      (fields
        (field (name "DB_PART_NUMBER") "CAP000022968")
        (field (name "DB_VALUE") "220nF")
        (field (name "DB_TOLERANCE") "10%")
        (field (name "DB_VOLTAGE") "25V")
        (field (name "DB_MANUFACTURER_PART") "KEMET    C0603F224K3RAC")
        (field (name "DB_APPROVED_BY") "ISHIDDEN=T")
      )
      (libsource (lib "Database_Libs1") (part "C"))
    )
    (comp (ref "C126")
      (value "10uF")
      (footprint "SMD_0805_CAPC2012X145N")
      (fields
        (field (name "DB_PART_NUMBER") "CAP000043636")
        (field (name "DB_VALUE") "10uF")
        (field (name "DB_TOLERANCE") "10%")
        (field (name "DB_VOLTAGE") "16V")
        (field (name "DB_MANUFACTURER_PART") "KEMET    C0805C106K4PAC")
        (field (name "DB_APPROVED_BY") "ISHIDDEN=T")
      )
      (libsource (lib "Database_Libs1") (part "C"))
    )
    (comp (ref "C127")
      (value "10uF")
      (footprint "SMD_0805_CAPC2012X145N")
      (fields
        (field (name "DB_PART_NUMBER") "CAP000043636")
        (field (name "DB_VALUE") "10uF")
        (field (name "DB_TOLERANCE") "10%")
        (field (name "DB_VOLTAGE") "16V")
        (field (name "DB_MANUFACTURER_PART") "KEMET    C0805C106K4PAC")
        (field (name "DB_APPROVED_BY") "ISHIDDEN=T")
      )
      (libsource (lib "Database_Libs1") (part "C"))
    )
    (comp (ref "C128")
      (value "22uF")
      (footprint "SMD_0805_CAPC2012X145N")
      (fields
        (field (name "DB_PART_NUMBER") "CAP000043686")
        (field (name "DB_VALUE") "22uF")
        (field (name "DB_TOLERANCE") "20%")
        (field (name "DB_MANUFACTURER_PART") "KEMET    C0805C226M9PAC")
        (field (name "DB_VOLTAGE") "6.3V")
        (field (name "DB_APPROVED_BY") "ISHIDDEN=T")
      )
      (libsource (lib "Database_Libs1") (part "C"))
    )
    (comp (ref "C130")
      (value "22uF")
      (footprint "SMD_0805_CAPC2012X145N")
      (fields
        (field (name "DB_PART_NUMBER") "CAP000043686")
        (field (name "DB_VALUE") "22uF")
        (field (name "DB_TOLERANCE") "20%")
        (field (name "DB_VOLTAGE") "6.3V")
        (field (name "DB_MANUFACTURER_PART") "KEMET    C0805C226M9PAC")
        (field (name "DB_APPROVED_BY") "ISHIDDEN=T")
      )
      (libsource (lib "Database_Libs1") (part "C"))
    )
    (comp (ref "C131")
      (value "22uF")
      (footprint "SMD_0805_CAPC2012X145N")
      (fields
        (field (name "DB_PART_NUMBER") "CAP000043686")
        (field (name "DB_VALUE") "22uF")
        (field (name "DB_TOLERANCE") "20%")
        (field (name "DB_VOLTAGE") "6.3V")
        (field (name "DB_MANUFACTURER_PART") "KEMET    C0805C226M9PAC")
        (field (name "DB_APPROVED_BY") "ISHIDDEN=T")
      )
      (libsource (lib "Database_Libs1") (part "C"))
    )
    (comp (ref "C132")
      (value "220uF")
      (footprint "SMD_1210_CAPC3225X279N")
      (fields
        (field (name "DB_PART_NUMBER") "CAP000047355")
        (field (name "DB_VALUE") "220uF")
        (field (name "DB_TOLERANCE") "20%")
        (field (name "DB_VOLTAGE") "6.3V")
        (field (name "DB_MANUFACTURER_PART") "SAMSUNG    CL32A227MQVNNNE")
        (field (name "DB_APPROVED_BY") "VSN")
      )
      (libsource (lib "Database_Libs1") (part "C"))
    )
    (comp (ref "C133")
      (value "100uF")
      (footprint "SMD_1210_CAPC3225X270N")
      (fields
        (field (name "DB_PART_NUMBER") "TMP-2512")
        (field (name "DB_VALUE") "100uF")
        (field (name "DB_TOLERANCE") "20%")
        (field (name "DB_VOLTAGE") "16V")
        (field (name "DB_MANUFACTURER_PART") "YAGEO    CC1210MRX5R7BB107")
      )
      (libsource (lib "Database_Libs1") (part "C"))
    )
    (comp (ref "C134")
      (value "100uF")
      (footprint "SMD_1210_CAPC3225X270N")
      (fields
        (field (name "DB_PART_NUMBER") "TMP-2512")
        (field (name "DB_VALUE") "100uF")
        (field (name "DB_TOLERANCE") "20%")
        (field (name "DB_VOLTAGE") "16V")
        (field (name "DB_MANUFACTURER_PART") "YAGEO    CC1210MRX5R7BB107")
      )
      (libsource (lib "Database_Libs1") (part "C"))
    )
    (comp (ref "C138")
      (value "22uF")
      (footprint "SMD_0805_CAPC2012X145N")
      (fields
        (field (name "DB_PART_NUMBER") "CAP000043686")
        (field (name "DB_VALUE") "22uF")
        (field (name "DB_TOLERANCE") "20%")
        (field (name "DB_VOLTAGE") "6.3V")
        (field (name "DB_MANUFACTURER_PART") "KEMET    C0805C226M9PAC")
        (field (name "DB_APPROVED_BY") "ISHIDDEN=T")
      )
      (libsource (lib "Database_Libs1") (part "C"))
    )
    (comp (ref "C139")
      (value "22uF")
      (footprint "SMD_0805_CAPC2012X145N")
      (fields
        (field (name "DB_PART_NUMBER") "CAP000043686")
        (field (name "DB_VALUE") "22uF")
        (field (name "DB_TOLERANCE") "20%")
        (field (name "DB_VOLTAGE") "6.3V")
        (field (name "DB_MANUFACTURER_PART") "KEMET    C0805C226M9PAC")
        (field (name "DB_APPROVED_BY") "ISHIDDEN=T")
      )
      (libsource (lib "Database_Libs1") (part "C"))
    )
    (comp (ref "C140")
      (value "220uF")
      (footprint "SMD_1210_CAPC3225X279N")
      (fields
        (field (name "DB_PART_NUMBER") "CAP000047355")
        (field (name "DB_VALUE") "220uF")
        (field (name "DB_TOLERANCE") "20%")
        (field (name "DB_VOLTAGE") "6.3V")
        (field (name "DB_MANUFACTURER_PART") "SAMSUNG    CL32A227MQVNNNE")
        (field (name "DB_APPROVED_BY") "VSN")
      )
      (libsource (lib "Database_Libs1") (part "C"))
    )
    (comp (ref "C141")
      (value "22uF")
      (footprint "SMD_0805_CAPC2012X145N")
      (fields
        (field (name "DB_PART_NUMBER") "CAP000043686")
        (field (name "DB_VALUE") "22uF")
        (field (name "DB_TOLERANCE") "20%")
        (field (name "DB_VOLTAGE") "6.3V")
        (field (name "DB_MANUFACTURER_PART") "KEMET    C0805C226M9PAC")
        (field (name "DB_APPROVED_BY") "ISHIDDEN=T")
      )
      (libsource (lib "Database_Libs1") (part "C"))
    )
    (comp (ref "C170")
      (value "22uF")
      (footprint "SMD_0805_CAPC2012X145N")
      (fields
        (field (name "DB_PART_NUMBER") "CAP000043686")
        (field (name "DB_VALUE") "22uF")
        (field (name "DB_TOLERANCE") "20%")
        (field (name "DB_VOLTAGE") "6.3V")
        (field (name "DB_MANUFACTURER_PART") "KEMET    C0805C226M9PAC")
        (field (name "DB_APPROVED_BY") "ISHIDDEN=T")
      )
      (libsource (lib "Database_Libs1") (part "C"))
    )
    (comp (ref "C172")
      (value "22uF")
      (footprint "SMD_0805_CAPC2012X145N")
      (fields
        (field (name "DB_PART_NUMBER") "CAP000043686")
        (field (name "DB_VALUE") "22uF")
        (field (name "DB_TOLERANCE") "20%")
        (field (name "DB_VOLTAGE") "6.3V")
        (field (name "DB_MANUFACTURER_PART") "KEMET    C0805C226M9PAC")
        (field (name "DB_APPROVED_BY") "ISHIDDEN=T")
      )
      (libsource (lib "Database_Libs1") (part "C"))
    )
    (comp (ref "C173")
      (value "22uF")
      (footprint "SMD_0805_CAPC2012X145N")
      (fields
        (field (name "DB_PART_NUMBER") "CAP000043686")
        (field (name "DB_VALUE") "22uF")
        (field (name "DB_TOLERANCE") "20%")
        (field (name "DB_VOLTAGE") "6.3V")
        (field (name "DB_MANUFACTURER_PART") "KEMET    C0805C226M9PAC")
        (field (name "DB_APPROVED_BY") "ISHIDDEN=T")
      )
      (libsource (lib "Database_Libs1") (part "C"))
    )
    (comp (ref "C174")
      (value "220uF")
      (footprint "SMD_1210_CAPC3225X279N")
      (fields
        (field (name "DB_PART_NUMBER") "CAP000047355")
        (field (name "DB_VALUE") "220uF")
        (field (name "DB_TOLERANCE") "20%")
        (field (name "DB_VOLTAGE") "6.3V")
        (field (name "DB_MANUFACTURER_PART") "SAMSUNG    CL32A227MQVNNNE")
        (field (name "DB_APPROVED_BY") "VSN")
      )
      (libsource (lib "Database_Libs1") (part "C"))
    )
    (comp (ref "C175")
      (value "22uF")
      (footprint "SMD_0805_CAPC2012X145N")
      (fields
        (field (name "DB_PART_NUMBER") "CAP000043686")
        (field (name "DB_VALUE") "22uF")
        (field (name "DB_TOLERANCE") "20%")
        (field (name "DB_VOLTAGE") "6.3V")
        (field (name "DB_MANUFACTURER_PART") "KEMET    C0805C226M9PAC")
        (field (name "DB_APPROVED_BY") "ISHIDDEN=T")
      )
      (libsource (lib "Database_Libs1") (part "C"))
    )
    (comp (ref "C176")
      (value "22uF")
      (footprint "SMD_0805_CAPC2012X145N")
      (fields
        (field (name "DB_PART_NUMBER") "CAP000043686")
        (field (name "DB_VALUE") "22uF")
        (field (name "DB_TOLERANCE") "20%")
        (field (name "DB_VOLTAGE") "6.3V")
        (field (name "DB_MANUFACTURER_PART") "KEMET    C0805C226M9PAC")
        (field (name "DB_APPROVED_BY") "ISHIDDEN=T")
      )
      (libsource (lib "Database_Libs1") (part "C"))
    )
    (comp (ref "C187")
      (value "22uF")
      (footprint "SMD_0805_CAPC2012X145N")
      (fields
        (field (name "DB_PART_NUMBER") "CAP000043686")
        (field (name "DB_VALUE") "22uF")
        (field (name "DB_TOLERANCE") "20%")
        (field (name "DB_VOLTAGE") "6.3V")
        (field (name "DB_MANUFACTURER_PART") "KEMET    C0805C226M9PAC")
        (field (name "DB_APPROVED_BY") "ISHIDDEN=T")
      )
      (libsource (lib "Database_Libs1") (part "C"))
    )
    (comp (ref "C197")
      (value "22uF")
      (footprint "SMD_0805_CAPC2012X145N")
      (fields
        (field (name "DB_PART_NUMBER") "CAP000043686")
        (field (name "DB_VALUE") "22uF")
        (field (name "DB_TOLERANCE") "20%")
        (field (name "DB_VOLTAGE") "6.3V")
        (field (name "DB_MANUFACTURER_PART") "KEMET    C0805C226M9PAC")
        (field (name "DB_APPROVED_BY") "ISHIDDEN=T")
      )
      (libsource (lib "Database_Libs1") (part "C"))
    )
    (comp (ref "C199")
      (value "22uF")
      (footprint "SMD_0805_CAPC2012X145N")
      (fields
        (field (name "DB_PART_NUMBER") "CAP000043686")
        (field (name "DB_VALUE") "22uF")
        (field (name "DB_TOLERANCE") "20%")
        (field (name "DB_VOLTAGE") "6.3V")
        (field (name "DB_MANUFACTURER_PART") "KEMET    C0805C226M9PAC")
        (field (name "DB_APPROVED_BY") "ISHIDDEN=T")
      )
      (libsource (lib "Database_Libs1") (part "C"))
    )
    (comp (ref "C200")
      (value "22uF")
      (footprint "SMD_0805_CAPC2012X145N")
      (fields
        (field (name "DB_PART_NUMBER") "CAP000043686")
        (field (name "DB_VALUE") "22uF")
        (field (name "DB_TOLERANCE") "20%")
        (field (name "DB_VOLTAGE") "6.3V")
        (field (name "DB_MANUFACTURER_PART") "KEMET    C0805C226M9PAC")
        (field (name "DB_APPROVED_BY") "ISHIDDEN=T")
      )
      (libsource (lib "Database_Libs1") (part "C"))
    )
    (comp (ref "C202")
      (value "22uF")
      (footprint "SMD_0805_CAPC2012X145N")
      (fields
        (field (name "DB_PART_NUMBER") "CAP000043686")
        (field (name "DB_VALUE") "22uF")
        (field (name "DB_TOLERANCE") "20%")
        (field (name "DB_VOLTAGE") "6.3V")
        (field (name "DB_MANUFACTURER_PART") "KEMET    C0805C226M9PAC")
        (field (name "DB_APPROVED_BY") "ISHIDDEN=T")
      )
      (libsource (lib "Database_Libs1") (part "C"))
    )
    (comp (ref "C203")
      (value "22uF")
      (footprint "SMD_0805_CAPC2012X145N")
      (fields
        (field (name "DB_PART_NUMBER") "CAP000043686")
        (field (name "DB_VALUE") "22uF")
        (field (name "DB_TOLERANCE") "20%")
        (field (name "DB_VOLTAGE") "6.3V")
        (field (name "DB_MANUFACTURER_PART") "KEMET    C0805C226M9PAC")
        (field (name "DB_APPROVED_BY") "ISHIDDEN=T")
      )
      (libsource (lib "Database_Libs1") (part "C"))
    )
    (comp (ref "C205")
      (value "22uF")
      (footprint "SMD_0805_CAPC2012X145N")
      (fields
        (field (name "DB_PART_NUMBER") "CAP000043686")
        (field (name "DB_VALUE") "22uF")
        (field (name "DB_TOLERANCE") "20%")
        (field (name "DB_VOLTAGE") "6.3V")
        (field (name "DB_MANUFACTURER_PART") "KEMET    C0805C226M9PAC")
        (field (name "DB_APPROVED_BY") "ISHIDDEN=T")
      )
      (libsource (lib "Database_Libs1") (part "C"))
    )
    (comp (ref "C257")
      (value "220nF")
      (footprint "SMD_0603_CAPC1608X95N")
      (fields
        (field (name "DB_PART_NUMBER") "CAP000022968")
        (field (name "DB_VALUE") "220nF")
        (field (name "DB_TOLERANCE") "10%")
        (field (name "DB_VOLTAGE") "25V")
        (field (name "DB_MANUFACTURER_PART") "KEMET    C0603F224K3RAC")
        (field (name "DB_APPROVED_BY") "ISHIDDEN=T")
      )
      (libsource (lib "Database_Libs1") (part "C"))
    )
    (comp (ref "C258")
      (value "100uF")
      (footprint "SMD_1210_CAPC3225X270N")
      (fields
        (field (name "DB_PART_NUMBER") "TMP-2512")
        (field (name "DB_VALUE") "100uF")
        (field (name "DB_TOLERANCE") "20%")
        (field (name "DB_VOLTAGE") "16V")
        (field (name "DB_MANUFACTURER_PART") "YAGEO    CC1210MRX5R7BB107")
      )
      (libsource (lib "Database_Libs1") (part "C"))
    )
    (comp (ref "C259")
      (value "100uF")
      (footprint "SMD_1210_CAPC3225X270N")
      (fields
        (field (name "DB_PART_NUMBER") "TMP-2512")
        (field (name "DB_VALUE") "100uF")
        (field (name "DB_TOLERANCE") "20%")
        (field (name "DB_VOLTAGE") "16V")
        (field (name "DB_MANUFACTURER_PART") "YAGEO    CC1210MRX5R7BB107")
      )
      (libsource (lib "Database_Libs1") (part "C"))
    )
    (comp (ref "C260")
      (value "220uF")
      (footprint "SMD_1210_CAPC3225X279N")
      (fields
        (field (name "DB_PART_NUMBER") "CAP000047355")
        (field (name "DB_VALUE") "220uF")
        (field (name "DB_TOLERANCE") "20%")
        (field (name "DB_VOLTAGE") "6.3V")
        (field (name "DB_MANUFACTURER_PART") "SAMSUNG    CL32A227MQVNNNE")
        (field (name "DB_APPROVED_BY") "VSN")
      )
      (libsource (lib "Database_Libs1") (part "C"))
    )
    (comp (ref "C261")
      (value "220uF")
      (footprint "SMD_1210_CAPC3225X279N")
      (fields
        (field (name "DB_PART_NUMBER") "CAP000047355")
        (field (name "DB_VALUE") "220uF")
        (field (name "DB_TOLERANCE") "20%")
        (field (name "DB_VOLTAGE") "6.3V")
        (field (name "DB_MANUFACTURER_PART") "SAMSUNG    CL32A227MQVNNNE")
        (field (name "DB_APPROVED_BY") "VSN")
      )
      (libsource (lib "Database_Libs1") (part "C"))
    )
    (comp (ref "C262")
      (value "220uF")
      (footprint "SMD_1210_CAPC3225X279N")
      (fields
        (field (name "DB_PART_NUMBER") "CAP000047355")
        (field (name "DB_VALUE") "220uF")
        (field (name "DB_TOLERANCE") "20%")
        (field (name "DB_VOLTAGE") "6.3V")
        (field (name "DB_MANUFACTURER_PART") "SAMSUNG    CL32A227MQVNNNE")
        (field (name "DB_APPROVED_BY") "VSN")
      )
      (libsource (lib "Database_Libs1") (part "C"))
    )
    (comp (ref "C263")
      (value "22uF")
      (footprint "SMD_0805_CAPC2012X145N")
      (fields
        (field (name "DB_PART_NUMBER") "CAP000043686")
        (field (name "DB_VALUE") "22uF")
        (field (name "DB_TOLERANCE") "20%")
        (field (name "DB_VOLTAGE") "6.3V")
        (field (name "DB_MANUFACTURER_PART") "KEMET    C0805C226M9PAC")
        (field (name "DB_APPROVED_BY") "ISHIDDEN=T")
      )
      (libsource (lib "Database_Libs1") (part "C"))
    )
    (comp (ref "C264")
      (value "22uF")
      (footprint "SMD_0805_CAPC2012X145N")
      (fields
        (field (name "DB_PART_NUMBER") "CAP000043686")
        (field (name "DB_VALUE") "22uF")
        (field (name "DB_TOLERANCE") "20%")
        (field (name "DB_VOLTAGE") "6.3V")
        (field (name "DB_MANUFACTURER_PART") "KEMET    C0805C226M9PAC")
        (field (name "DB_APPROVED_BY") "ISHIDDEN=T")
      )
      (libsource (lib "Database_Libs1") (part "C"))
    )
    (comp (ref "C265")
      (value "22uF")
      (footprint "SMD_0805_CAPC2012X145N")
      (fields
        (field (name "DB_PART_NUMBER") "CAP000043686")
        (field (name "DB_VALUE") "22uF")
        (field (name "DB_TOLERANCE") "20%")
        (field (name "DB_VOLTAGE") "6.3V")
        (field (name "DB_MANUFACTURER_PART") "KEMET    C0805C226M9PAC")
        (field (name "DB_APPROVED_BY") "ISHIDDEN=T")
      )
      (libsource (lib "Database_Libs1") (part "C"))
    )
    (comp (ref "C266")
      (value "22uF")
      (footprint "SMD_0805_CAPC2012X145N")
      (fields
        (field (name "DB_PART_NUMBER") "CAP000043686")
        (field (name "DB_VALUE") "22uF")
        (field (name "DB_TOLERANCE") "20%")
        (field (name "DB_VOLTAGE") "6.3V")
        (field (name "DB_MANUFACTURER_PART") "KEMET    C0805C226M9PAC")
        (field (name "DB_APPROVED_BY") "ISHIDDEN=T")
      )
      (libsource (lib "Database_Libs1") (part "C"))
    )
    (comp (ref "C267")
      (value "220uF")
      (footprint "SMD_1210_CAPC3225X279N")
      (fields
        (field (name "DB_PART_NUMBER") "CAP000047355")
        (field (name "DB_VALUE") "220uF")
        (field (name "DB_TOLERANCE") "20%")
        (field (name "DB_VOLTAGE") "6.3V")
        (field (name "DB_MANUFACTURER_PART") "SAMSUNG    CL32A227MQVNNNE")
        (field (name "DB_APPROVED_BY") "VSN")
      )
      (libsource (lib "Database_Libs1") (part "C"))
    )
    (comp (ref "C268")
      (value "22uF")
      (footprint "SMD_0805_CAPC2012X145N")
      (fields
        (field (name "DB_PART_NUMBER") "CAP000043686")
        (field (name "DB_VALUE") "22uF")
        (field (name "DB_TOLERANCE") "20%")
        (field (name "DB_VOLTAGE") "6.3V")
        (field (name "DB_MANUFACTURER_PART") "KEMET    C0805C226M9PAC")
        (field (name "DB_APPROVED_BY") "ISHIDDEN=T")
      )
      (libsource (lib "Database_Libs1") (part "C"))
    )
    (comp (ref "C269")
      (value "22uF")
      (footprint "SMD_0805_CAPC2012X145N")
      (fields
        (field (name "DB_PART_NUMBER") "CAP000043686")
        (field (name "DB_VALUE") "22uF")
        (field (name "DB_TOLERANCE") "20%")
        (field (name "DB_VOLTAGE") "6.3V")
        (field (name "DB_MANUFACTURER_PART") "KEMET    C0805C226M9PAC")
        (field (name "DB_APPROVED_BY") "ISHIDDEN=T")
      )
      (libsource (lib "Database_Libs1") (part "C"))
    )
    (comp (ref "C270")
      (value "220uF")
      (footprint "SMD_1210_CAPC3225X279N")
      (fields
        (field (name "DB_PART_NUMBER") "CAP000047355")
        (field (name "DB_VALUE") "220uF")
        (field (name "DB_TOLERANCE") "20%")
        (field (name "DB_VOLTAGE") "6.3V")
        (field (name "DB_MANUFACTURER_PART") "SAMSUNG    CL32A227MQVNNNE")
        (field (name "DB_APPROVED_BY") "VSN")
      )
      (libsource (lib "Database_Libs1") (part "C"))
    )
    (comp (ref "C271")
      (value "22uF")
      (footprint "SMD_0805_CAPC2012X145N")
      (fields
        (field (name "DB_PART_NUMBER") "CAP000043686")
        (field (name "DB_VALUE") "22uF")
        (field (name "DB_TOLERANCE") "20%")
        (field (name "DB_VOLTAGE") "6.3V")
        (field (name "DB_MANUFACTURER_PART") "KEMET    C0805C226M9PAC")
        (field (name "DB_APPROVED_BY") "ISHIDDEN=T")
      )
      (libsource (lib "Database_Libs1") (part "C"))
    )
    (comp (ref "C272")
      (value "22uF")
      (footprint "SMD_0805_CAPC2012X145N")
      (fields
        (field (name "DB_PART_NUMBER") "CAP000043686")
        (field (name "DB_VALUE") "22uF")
        (field (name "DB_TOLERANCE") "20%")
        (field (name "DB_VOLTAGE") "6.3V")
        (field (name "DB_MANUFACTURER_PART") "KEMET    C0805C226M9PAC")
        (field (name "DB_APPROVED_BY") "ISHIDDEN=T")
      )
      (libsource (lib "Database_Libs1") (part "C"))
    )
    (comp (ref "C273")
      (value "220uF")
      (footprint "SMD_1210_CAPC3225X279N")
      (fields
        (field (name "DB_PART_NUMBER") "CAP000047355")
        (field (name "DB_VALUE") "220uF")
        (field (name "DB_TOLERANCE") "20%")
        (field (name "DB_VOLTAGE") "6.3V")
        (field (name "DB_MANUFACTURER_PART") "SAMSUNG    CL32A227MQVNNNE")
        (field (name "DB_APPROVED_BY") "VSN")
      )
      (libsource (lib "Database_Libs1") (part "C"))
    )
    (comp (ref "C274")
      (value "22uF")
      (footprint "SMD_0805_CAPC2012X145N")
      (fields
        (field (name "DB_PART_NUMBER") "CAP000043686")
        (field (name "DB_VALUE") "22uF")
        (field (name "DB_TOLERANCE") "20%")
        (field (name "DB_VOLTAGE") "6.3V")
        (field (name "DB_MANUFACTURER_PART") "KEMET    C0805C226M9PAC")
        (field (name "DB_APPROVED_BY") "ISHIDDEN=T")
      )
      (libsource (lib "Database_Libs1") (part "C"))
    )
    (comp (ref "C275")
      (value "22uF")
      (footprint "SMD_0805_CAPC2012X145N")
      (fields
        (field (name "DB_PART_NUMBER") "CAP000043686")
        (field (name "DB_VALUE") "22uF")
        (field (name "DB_TOLERANCE") "20%")
        (field (name "DB_VOLTAGE") "6.3V")
        (field (name "DB_MANUFACTURER_PART") "KEMET    C0805C226M9PAC")
        (field (name "DB_APPROVED_BY") "ISHIDDEN=T")
      )
      (libsource (lib "Database_Libs1") (part "C"))
    )
    (comp (ref "C276")
      (value "220uF")
      (footprint "SMD_1210_CAPC3225X279N")
      (fields
        (field (name "DB_PART_NUMBER") "CAP000047355")
        (field (name "DB_VALUE") "220uF")
        (field (name "DB_TOLERANCE") "20%")
        (field (name "DB_VOLTAGE") "6.3V")
        (field (name "DB_MANUFACTURER_PART") "SAMSUNG    CL32A227MQVNNNE")
        (field (name "DB_APPROVED_BY") "VSN")
      )
      (libsource (lib "Database_Libs1") (part "C"))
    )
    (comp (ref "C331")
      (value "22uF")
      (footprint "SMD_0805_CAPC2012X145N")
      (fields
        (field (name "DB_PART_NUMBER") "CAP000043686")
        (field (name "DB_VALUE") "22uF")
        (field (name "DB_TOLERANCE") "20%")
        (field (name "DB_VOLTAGE") "6.3V")
        (field (name "DB_MANUFACTURER_PART") "KEMET    C0805C226M9PAC")
        (field (name "DB_APPROVED_BY") "ISHIDDEN=T")
      )
      (libsource (lib "Database_Libs1") (part "C"))
    )
    (comp (ref "C332")
      (value "22uF")
      (footprint "SMD_0805_CAPC2012X145N")
      (fields
        (field (name "DB_PART_NUMBER") "CAP000043686")
        (field (name "DB_VALUE") "22uF")
        (field (name "DB_TOLERANCE") "20%")
        (field (name "DB_VOLTAGE") "6.3V")
        (field (name "DB_MANUFACTURER_PART") "KEMET    C0805C226M9PAC")
        (field (name "DB_APPROVED_BY") "ISHIDDEN=T")
      )
      (libsource (lib "Database_Libs1") (part "C"))
    )
    (comp (ref "C333")
      (value "22uF")
      (footprint "SMD_0805_CAPC2012X145N")
      (fields
        (field (name "DB_PART_NUMBER") "CAP000043686")
        (field (name "DB_VALUE") "22uF")
        (field (name "DB_TOLERANCE") "20%")
        (field (name "DB_VOLTAGE") "6.3V")
        (field (name "DB_MANUFACTURER_PART") "KEMET    C0805C226M9PAC")
        (field (name "DB_APPROVED_BY") "ISHIDDEN=T")
      )
      (libsource (lib "Database_Libs1") (part "C"))
    )
    (comp (ref "C334")
      (value "22uF")
      (footprint "SMD_0805_CAPC2012X145N")
      (fields
        (field (name "DB_PART_NUMBER") "CAP000043686")
        (field (name "DB_VALUE") "22uF")
        (field (name "DB_TOLERANCE") "20%")
        (field (name "DB_VOLTAGE") "6.3V")
        (field (name "DB_MANUFACTURER_PART") "KEMET    C0805C226M9PAC")
        (field (name "DB_APPROVED_BY") "ISHIDDEN=T")
      )
      (libsource (lib "Database_Libs1") (part "C"))
    )
    (comp (ref "C373")
      (value "100uF")
      (footprint "SMD_1210_CAPC3225X270N")
      (fields
        (field (name "DB_PART_NUMBER") "TMP-2512")
        (field (name "DB_VALUE") "100uF")
        (field (name "DB_TOLERANCE") "20%")
        (field (name "DB_VOLTAGE") "16V")
        (field (name "DB_MANUFACTURER_PART") "YAGEO    CC1210MRX5R7BB107")
      )
      (libsource (lib "Database_Libs1") (part "C"))
    )
    (comp (ref "C374")
      (value "100uF")
      (footprint "SMD_1210_CAPC3225X270N")
      (fields
        (field (name "DB_PART_NUMBER") "TMP-2512")
        (field (name "DB_VALUE") "100uF")
        (field (name "DB_TOLERANCE") "20%")
        (field (name "DB_VOLTAGE") "16V")
        (field (name "DB_MANUFACTURER_PART") "YAGEO    CC1210MRX5R7BB107")
      )
      (libsource (lib "Database_Libs1") (part "C"))
    )
    (comp (ref "C375")
      (value "220uF")
      (footprint "SMD_1210_CAPC3225X279N")
      (fields
        (field (name "DB_PART_NUMBER") "CAP000047355")
        (field (name "DB_VALUE") "220uF")
        (field (name "DB_TOLERANCE") "20%")
        (field (name "DB_VOLTAGE") "6.3V")
        (field (name "DB_MANUFACTURER_PART") "SAMSUNG    CL32A227MQVNNNE")
        (field (name "DB_APPROVED_BY") "VSN")
      )
      (libsource (lib "Database_Libs1") (part "C"))
    )
    (comp (ref "C376")
      (value "220uF")
      (footprint "SMD_1210_CAPC3225X279N")
      (fields
        (field (name "DB_PART_NUMBER") "CAP000047355")
        (field (name "DB_VALUE") "220uF")
        (field (name "DB_TOLERANCE") "20%")
        (field (name "DB_VOLTAGE") "6.3V")
        (field (name "DB_MANUFACTURER_PART") "SAMSUNG    CL32A227MQVNNNE")
        (field (name "DB_APPROVED_BY") "VSN")
      )
      (libsource (lib "Database_Libs1") (part "C"))
    )
    (comp (ref "C377")
      (value "220uF")
      (footprint "SMD_1210_CAPC3225X279N")
      (fields
        (field (name "DB_PART_NUMBER") "CAP000047355")
        (field (name "DB_VALUE") "220uF")
        (field (name "DB_TOLERANCE") "20%")
        (field (name "DB_VOLTAGE") "6.3V")
        (field (name "DB_MANUFACTURER_PART") "SAMSUNG    CL32A227MQVNNNE")
        (field (name "DB_APPROVED_BY") "VSN")
      )
      (libsource (lib "Database_Libs1") (part "C"))
    )
    (comp (ref "C378")
      (value "10uF")
      (footprint "SMD_0805_CAPC2012X145N")
      (fields
        (field (name "DB_PART_NUMBER") "CAP000043636")
        (field (name "DB_VALUE") "10uF")
        (field (name "DB_TOLERANCE") "10%")
        (field (name "DB_VOLTAGE") "16V")
        (field (name "DB_MANUFACTURER_PART") "KEMET    C0805C106K4PAC")
        (field (name "DB_APPROVED_BY") "ISHIDDEN=T")
      )
      (libsource (lib "Database_Libs1") (part "C"))
    )
    (comp (ref "C379")
      (value "10uF")
      (footprint "SMD_0805_CAPC2012X145N")
      (fields
        (field (name "DB_PART_NUMBER") "CAP000043636")
        (field (name "DB_VALUE") "10uF")
        (field (name "DB_TOLERANCE") "10%")
        (field (name "DB_VOLTAGE") "16V")
        (field (name "DB_MANUFACTURER_PART") "KEMET    C0805C106K4PAC")
        (field (name "DB_APPROVED_BY") "ISHIDDEN=T")
      )
      (libsource (lib "Database_Libs1") (part "C"))
    )
    (comp (ref "C380")
      (value "10uF")
      (footprint "SMD_0805_CAPC2012X145N")
      (fields
        (field (name "DB_PART_NUMBER") "CAP000043636")
        (field (name "DB_VALUE") "10uF")
        (field (name "DB_TOLERANCE") "10%")
        (field (name "DB_VOLTAGE") "16V")
        (field (name "DB_MANUFACTURER_PART") "KEMET    C0805C106K4PAC")
        (field (name "DB_APPROVED_BY") "ISHIDDEN=T")
      )
      (libsource (lib "Database_Libs1") (part "C"))
    )
    (comp (ref "C381")
      (value "220uF")
      (footprint "SMD_1210_CAPC3225X279N")
      (fields
        (field (name "DB_PART_NUMBER") "CAP000047355")
        (field (name "DB_VALUE") "220uF")
        (field (name "DB_TOLERANCE") "20%")
        (field (name "DB_VOLTAGE") "6.3V")
        (field (name "DB_MANUFACTURER_PART") "SAMSUNG    CL32A227MQVNNNE")
        (field (name "DB_APPROVED_BY") "VSN")
      )
      (libsource (lib "Database_Libs1") (part "C"))
    )
    (comp (ref "C382")
      (value "220uF")
      (footprint "SMD_1210_CAPC3225X279N")
      (fields
        (field (name "DB_PART_NUMBER") "CAP000047355")
        (field (name "DB_VALUE") "220uF")
        (field (name "DB_TOLERANCE") "20%")
        (field (name "DB_VOLTAGE") "6.3V")
        (field (name "DB_MANUFACTURER_PART") "SAMSUNG    CL32A227MQVNNNE")
        (field (name "DB_APPROVED_BY") "VSN")
      )
      (libsource (lib "Database_Libs1") (part "C"))
    )
    (comp (ref "C397")
      (value "220uF")
      (footprint "SMD_1210_CAPC3225X279N")
      (fields
        (field (name "DB_PART_NUMBER") "CAP000047355")
        (field (name "DB_VALUE") "220uF")
        (field (name "DB_TOLERANCE") "20%")
        (field (name "DB_VOLTAGE") "6.3V")
        (field (name "DB_MANUFACTURER_PART") "SAMSUNG    CL32A227MQVNNNE")
        (field (name "DB_APPROVED_BY") "VSN")
      )
      (libsource (lib "Database_Libs1") (part "C"))
    )
    (comp (ref "C398")
      (value "220uF")
      (footprint "SMD_1210_CAPC3225X279N")
      (fields
        (field (name "DB_PART_NUMBER") "CAP000047355")
        (field (name "DB_VALUE") "220uF")
        (field (name "DB_TOLERANCE") "20%")
        (field (name "DB_VOLTAGE") "6.3V")
        (field (name "DB_MANUFACTURER_PART") "SAMSUNG    CL32A227MQVNNNE")
        (field (name "DB_APPROVED_BY") "VSN")
      )
      (libsource (lib "Database_Libs1") (part "C"))
    )
    (comp (ref "C399")
      (value "220uF")
      (footprint "SMD_1210_CAPC3225X279N")
      (fields
        (field (name "DB_PART_NUMBER") "CAP000047355")
        (field (name "DB_VALUE") "220uF")
        (field (name "DB_TOLERANCE") "20%")
        (field (name "DB_VOLTAGE") "6.3V")
        (field (name "DB_MANUFACTURER_PART") "SAMSUNG    CL32A227MQVNNNE")
        (field (name "DB_APPROVED_BY") "VSN")
      )
      (libsource (lib "Database_Libs1") (part "C"))
    )
    (comp (ref "C400")
      (value "220uF")
      (footprint "SMD_1210_CAPC3225X279N")
      (fields
        (field (name "DB_PART_NUMBER") "CAP000047355")
        (field (name "DB_VALUE") "220uF")
        (field (name "DB_TOLERANCE") "20%")
        (field (name "DB_VOLTAGE") "6.3V")
        (field (name "DB_MANUFACTURER_PART") "SAMSUNG    CL32A227MQVNNNE")
        (field (name "DB_APPROVED_BY") "VSN")
      )
      (libsource (lib "Database_Libs1") (part "C"))
    )
    (comp (ref "C401")
      (value "220uF")
      (footprint "SMD_1210_CAPC3225X279N")
      (fields
        (field (name "DB_PART_NUMBER") "CAP000047355")
        (field (name "DB_VALUE") "220uF")
        (field (name "DB_TOLERANCE") "20%")
        (field (name "DB_VOLTAGE") "6.3V")
        (field (name "DB_MANUFACTURER_PART") "SAMSUNG    CL32A227MQVNNNE")
        (field (name "DB_APPROVED_BY") "VSN")
      )
      (libsource (lib "Database_Libs1") (part "C"))
    )
    (comp (ref "C404")
      (value "100uF")
      (footprint "SMD_1210_CAPC3225X270N")
      (fields
        (field (name "DB_PART_NUMBER") "TMP-2512")
        (field (name "DB_VALUE") "100uF")
        (field (name "DB_TOLERANCE") "20%")
        (field (name "DB_VOLTAGE") "16V")
        (field (name "DB_MANUFACTURER_PART") "YAGEO    CC1210MRX5R7BB107")
      )
      (libsource (lib "Database_Libs1") (part "C"))
    )
    (comp (ref "C405")
      (value "100uF")
      (footprint "SMD_1210_CAPC3225X270N")
      (fields
        (field (name "DB_PART_NUMBER") "TMP-2512")
        (field (name "DB_VALUE") "100uF")
        (field (name "DB_TOLERANCE") "20%")
        (field (name "DB_VOLTAGE") "16V")
        (field (name "DB_MANUFACTURER_PART") "YAGEO    CC1210MRX5R7BB107")
      )
      (libsource (lib "Database_Libs1") (part "C"))
    )
    (comp (ref "C406")
      (value "100uF")
      (footprint "SMD_1210_CAPC3225X270N")
      (fields
        (field (name "DB_PART_NUMBER") "TMP-2512")
        (field (name "DB_VALUE") "100uF")
        (field (name "DB_TOLERANCE") "20%")
        (field (name "DB_VOLTAGE") "16V")
        (field (name "DB_MANUFACTURER_PART") "YAGEO    CC1210MRX5R7BB107")
      )
      (libsource (lib "Database_Libs1") (part "C"))
    )
    (comp (ref "C407")
      (value "100uF")
      (footprint "SMD_1210_CAPC3225X270N")
      (fields
        (field (name "DB_PART_NUMBER") "TMP-2512")
        (field (name "DB_VALUE") "100uF")
        (field (name "DB_TOLERANCE") "20%")
        (field (name "DB_VOLTAGE") "16V")
        (field (name "DB_MANUFACTURER_PART") "YAGEO    CC1210MRX5R7BB107")
      )
      (libsource (lib "Database_Libs1") (part "C"))
    )
    (comp (ref "C596")
      (value "100uF")
      (footprint "SMD_1210_CAPC3225X270N")
      (fields
        (field (name "DB_PART_NUMBER") "TMP-2512")
        (field (name "DB_VALUE") "100uF")
        (field (name "DB_TOLERANCE") "20%")
        (field (name "DB_VOLTAGE") "16V")
        (field (name "DB_MANUFACTURER_PART") "YAGEO    CC1210MRX5R7BB107")
      )
      (libsource (lib "Database_Libs1") (part "C"))
    )
    (comp (ref "C598")
      (value "10uF")
      (footprint "SMD_0805_CAPC2012X145N")
      (fields
        (field (name "DB_PART_NUMBER") "CAP000043636")
        (field (name "DB_VALUE") "10uF")
        (field (name "DB_TOLERANCE") "10%")
        (field (name "DB_VOLTAGE") "16V")
        (field (name "DB_MANUFACTURER_PART") "KEMET    C0805C106K4PAC")
        (field (name "DB_APPROVED_BY") "ISHIDDEN=T")
      )
      (libsource (lib "Database_Libs1") (part "C"))
    )
    (comp (ref "C599")
      (value "100uF")
      (footprint "SMD_1210_CAPC3225X270N")
      (fields
        (field (name "DB_PART_NUMBER") "TMP-2512")
        (field (name "DB_VALUE") "100uF")
        (field (name "DB_TOLERANCE") "20%")
        (field (name "DB_VOLTAGE") "16V")
        (field (name "DB_MANUFACTURER_PART") "YAGEO    CC1210MRX5R7BB107")
      )
      (libsource (lib "Database_Libs1") (part "C"))
    )
    (comp (ref "C600")
      (value "10uF")
      (footprint "SMD_0805_CAPC2012X145N")
      (fields
        (field (name "DB_PART_NUMBER") "CAP000043636")
        (field (name "DB_VALUE") "10uF")
        (field (name "DB_TOLERANCE") "10%")
        (field (name "DB_VOLTAGE") "16V")
        (field (name "DB_MANUFACTURER_PART") "KEMET    C0805C106K4PAC")
        (field (name "DB_APPROVED_BY") "ISHIDDEN=T")
      )
      (libsource (lib "Database_Libs1") (part "C"))
    )
    (comp (ref "C602")
      (value "100uF")
      (footprint "SMD_1210_CAPC3225X270N")
      (fields
        (field (name "DB_PART_NUMBER") "TMP-2512")
        (field (name "DB_VALUE") "100uF")
        (field (name "DB_TOLERANCE") "20%")
        (field (name "DB_VOLTAGE") "16V")
        (field (name "DB_MANUFACTURER_PART") "YAGEO    CC1210MRX5R7BB107")
      )
      (libsource (lib "Database_Libs1") (part "C"))
    )
    (comp (ref "C603")
      (value "10uF")
      (footprint "SMD_0805_CAPC2012X145N")
      (fields
        (field (name "DB_PART_NUMBER") "CAP000043636")
        (field (name "DB_VALUE") "10uF")
        (field (name "DB_TOLERANCE") "10%")
        (field (name "DB_VOLTAGE") "16V")
        (field (name "DB_MANUFACTURER_PART") "KEMET    C0805C106K4PAC")
        (field (name "DB_APPROVED_BY") "ISHIDDEN=T")
      )
      (libsource (lib "Database_Libs1") (part "C"))
    )
    (comp (ref "C605")
      (value "100uF")
      (footprint "SMD_1210_CAPC3225X270N")
      (fields
        (field (name "DB_PART_NUMBER") "TMP-2512")
        (field (name "DB_VALUE") "100uF")
        (field (name "DB_TOLERANCE") "20%")
        (field (name "DB_VOLTAGE") "16V")
        (field (name "DB_MANUFACTURER_PART") "YAGEO    CC1210MRX5R7BB107")
      )
      (libsource (lib "Database_Libs1") (part "C"))
    )
    (comp (ref "C606")
      (value "10uF")
      (footprint "SMD_0805_CAPC2012X145N")
      (fields
        (field (name "DB_PART_NUMBER") "CAP000043636")
        (field (name "DB_VALUE") "10uF")
        (field (name "DB_TOLERANCE") "10%")
        (field (name "DB_VOLTAGE") "16V")
        (field (name "DB_MANUFACTURER_PART") "KEMET    C0805C106K4PAC")
        (field (name "DB_APPROVED_BY") "ISHIDDEN=T")
      )
      (libsource (lib "Database_Libs1") (part "C"))
    )
    (comp (ref "C640")
      (value "10uF")
      (footprint "SMD_0805_CAPC2012X145N")
      (fields
        (field (name "DB_PART_NUMBER") "CAP000043636")
        (field (name "DB_VALUE") "10uF")
        (field (name "DB_TOLERANCE") "10%")
        (field (name "DB_VOLTAGE") "16V")
        (field (name "DB_MANUFACTURER_PART") "KEMET    C0805C106K4PAC")
        (field (name "DB_APPROVED_BY") "ISHIDDEN=T")
      )
      (libsource (lib "Database_Libs1") (part "C"))
    )
    (comp (ref "C642")
      (value "10uF")
      (footprint "SMD_0805_CAPC2012X145N")
      (fields
        (field (name "DB_PART_NUMBER") "CAP000043636")
        (field (name "DB_VALUE") "10uF")
        (field (name "DB_TOLERANCE") "10%")
        (field (name "DB_VOLTAGE") "16V")
        (field (name "DB_MANUFACTURER_PART") "KEMET    C0805C106K4PAC")
        (field (name "DB_APPROVED_BY") "ISHIDDEN=T")
      )
      (libsource (lib "Database_Libs1") (part "C"))
    )
    (comp (ref "C652")
      (value "22uF")
      (footprint "SMD_0805_CAPC2012X145N")
      (fields
        (field (name "DB_PART_NUMBER") "CAP000043686")
        (field (name "DB_VALUE") "22uF")
        (field (name "DB_TOLERANCE") "20%")
        (field (name "DB_VOLTAGE") "6.3V")
        (field (name "DB_MANUFACTURER_PART") "KEMET    C0805C226M9PAC")
        (field (name "DB_APPROVED_BY") "ISHIDDEN=T")
      )
      (libsource (lib "Database_Libs1") (part "C"))
    )
    (comp (ref "C653")
      (value "220uF")
      (footprint "SMD_1210_CAPC3225X279N")
      (fields
        (field (name "DB_PART_NUMBER") "CAP000047355")
        (field (name "DB_VALUE") "220uF")
        (field (name "DB_TOLERANCE") "20%")
        (field (name "DB_VOLTAGE") "6.3V")
        (field (name "DB_MANUFACTURER_PART") "SAMSUNG    CL32A227MQVNNNE")
        (field (name "DB_APPROVED_BY") "VSN")
      )
      (libsource (lib "Database_Libs1") (part "C"))
    )
    (comp (ref "C654")
      (value "22uF")
      (footprint "SMD_0805_CAPC2012X145N")
      (fields
        (field (name "DB_PART_NUMBER") "CAP000043686")
        (field (name "DB_VALUE") "22uF")
        (field (name "DB_TOLERANCE") "20%")
        (field (name "DB_VOLTAGE") "6.3V")
        (field (name "DB_MANUFACTURER_PART") "KEMET    C0805C226M9PAC")
        (field (name "DB_APPROVED_BY") "ISHIDDEN=T")
      )
      (libsource (lib "Database_Libs1") (part "C"))
    )
    (comp (ref "C655")
      (value "22uF")
      (footprint "SMD_0805_CAPC2012X145N")
      (fields
        (field (name "DB_PART_NUMBER") "CAP000043686")
        (field (name "DB_VALUE") "22uF")
        (field (name "DB_TOLERANCE") "20%")
        (field (name "DB_VOLTAGE") "6.3V")
        (field (name "DB_MANUFACTURER_PART") "KEMET    C0805C226M9PAC")
        (field (name "DB_APPROVED_BY") "ISHIDDEN=T")
      )
      (libsource (lib "Database_Libs1") (part "C"))
    )
    (comp (ref "C656")
      (value "220uF")
      (footprint "SMD_1210_CAPC3225X279N")
      (fields
        (field (name "DB_PART_NUMBER") "CAP000047355")
        (field (name "DB_VALUE") "220uF")
        (field (name "DB_TOLERANCE") "20%")
        (field (name "DB_VOLTAGE") "6.3V")
        (field (name "DB_MANUFACTURER_PART") "SAMSUNG    CL32A227MQVNNNE")
        (field (name "DB_APPROVED_BY") "VSN")
      )
      (libsource (lib "Database_Libs1") (part "C"))
    )
    (comp (ref "C657")
      (value "22uF")
      (footprint "SMD_0805_CAPC2012X145N")
      (fields
        (field (name "DB_PART_NUMBER") "CAP000043686")
        (field (name "DB_VALUE") "22uF")
        (field (name "DB_TOLERANCE") "20%")
        (field (name "DB_VOLTAGE") "6.3V")
        (field (name "DB_MANUFACTURER_PART") "KEMET    C0805C226M9PAC")
        (field (name "DB_APPROVED_BY") "ISHIDDEN=T")
      )
      (libsource (lib "Database_Libs1") (part "C"))
    )
    (comp (ref "C658")
      (value "22uF")
      (footprint "SMD_0805_CAPC2012X145N")
      (fields
        (field (name "DB_PART_NUMBER") "CAP000043686")
        (field (name "DB_VALUE") "22uF")
        (field (name "DB_TOLERANCE") "20%")
        (field (name "DB_VOLTAGE") "6.3V")
        (field (name "DB_MANUFACTURER_PART") "KEMET    C0805C226M9PAC")
        (field (name "DB_APPROVED_BY") "ISHIDDEN=T")
      )
      (libsource (lib "Database_Libs1") (part "C"))
    )
    (comp (ref "C659")
      (value "220uF")
      (footprint "SMD_1210_CAPC3225X279N")
      (fields
        (field (name "DB_PART_NUMBER") "CAP000047355")
        (field (name "DB_VALUE") "220uF")
        (field (name "DB_TOLERANCE") "20%")
        (field (name "DB_VOLTAGE") "6.3V")
        (field (name "DB_MANUFACTURER_PART") "SAMSUNG    CL32A227MQVNNNE")
        (field (name "DB_APPROVED_BY") "VSN")
      )
      (libsource (lib "Database_Libs1") (part "C"))
    )
    (comp (ref "C660")
      (value "22uF")
      (footprint "SMD_0805_CAPC2012X145N")
      (fields
        (field (name "DB_PART_NUMBER") "CAP000043686")
        (field (name "DB_VALUE") "22uF")
        (field (name "DB_TOLERANCE") "20%")
        (field (name "DB_VOLTAGE") "6.3V")
        (field (name "DB_MANUFACTURER_PART") "KEMET    C0805C226M9PAC")
        (field (name "DB_APPROVED_BY") "ISHIDDEN=T")
      )
      (libsource (lib "Database_Libs1") (part "C"))
    )
    (comp (ref "C711")
      (value "10uF")
      (footprint "SMD_0805_CAPC2012X145N")
      (fields
        (field (name "DB_PART_NUMBER") "CAP000043636")
        (field (name "DB_VALUE") "10uF")
        (field (name "DB_TOLERANCE") "10%")
        (field (name "DB_VOLTAGE") "16V")
        (field (name "DB_MANUFACTURER_PART") "KEMET    C0805C106K4PAC")
        (field (name "DB_APPROVED_BY") "ISHIDDEN=T")
      )
      (libsource (lib "Database_Libs1") (part "C"))
    )
    (comp (ref "C814")
      (value "10uF")
      (footprint "SMD_0805_CAPC2012X145N")
      (fields
        (field (name "DB_PART_NUMBER") "CAP000043636")
        (field (name "DB_VALUE") "10uF")
        (field (name "DB_TOLERANCE") "10%")
        (field (name "DB_VOLTAGE") "16V")
        (field (name "DB_MANUFACTURER_PART") "KEMET    C0805C106K4PAC")
        (field (name "DB_APPROVED_BY") "ISHIDDEN=T")
      )
      (libsource (lib "Database_Libs1") (part "C"))
    )
    (comp (ref "L3")
      (value "~")
      (footprint "SMT_INDM135130X800N")
      (libsource (lib "EPIQ_DND_CIS_Library") (part "L"))
    )
    (comp (ref "L7")
      (value "~")
      (footprint "SMT_INDM135130X800N")
      (libsource (lib "EPIQ_DND_CIS_Library") (part "L"))
    )
    (comp (ref "L10")
      (value "~")
      (footprint "SMT_INDM135130X800N")
      (libsource (lib "EPIQ_DND_CIS_Library") (part "L"))
    )
    (comp (ref "L14")
      (value "~")
      (footprint "SMT_INDM135130X800N")
      (libsource (lib "EPIQ_DND_CIS_Library") (part "L"))
    )
    (comp (ref "R1")
      (value "10k")
      (footprint "SMD_0603_RESC1608X55N")
      (fields
        (field (name "DB_PART_NUMBER") "RES000008663")
        (field (name "DB_VALUE") "10k")
        (field (name "DB_TOLERANCE") "1%")
        (field (name "DB_MANUFACTURER_PART") "YAGEO    RC0603FR-0710KL")
        (field (name "DB_APPROVED_BY") "VSN")
      )
      (libsource (lib "Database_Libs1") (part "R"))
    )
    (comp (ref "R2")
      (value "10k")
      (footprint "SMD_0603_RESC1608X55N")
      (fields
        (field (name "DB_PART_NUMBER") "RES000008663")
        (field (name "DB_VALUE") "10k")
        (field (name "DB_TOLERANCE") "1%")
        (field (name "DB_MANUFACTURER_PART") "YAGEO    RC0603FR-0710KL")
        (field (name "DB_APPROVED_BY") "VSN")
      )
      (libsource (lib "Database_Libs1") (part "R"))
    )
    (comp (ref "R3")
      (value "100R")
      (footprint "SMD_0603_RESC1608X55N")
      (fields
        (field (name "DB_PART_NUMBER") "RES000006398")
        (field (name "DB_VALUE") "100R")
        (field (name "DB_TOLERANCE") "5%")
        (field (name "DB_MANUFACTURER_PART") "YAGEO    RC0603JR-07100R")
        (field (name "DB_APPROVED_BY") "ISHIDDEN=T")
      )
      (libsource (lib "Database_Libs1") (part "R"))
    )
    (comp (ref "R4")
      (value "100R")
      (footprint "SMD_0603_RESC1608X55N")
      (fields
        (field (name "DB_PART_NUMBER") "RES000006398")
        (field (name "DB_VALUE") "100R")
        (field (name "DB_TOLERANCE") "5%")
        (field (name "DB_MANUFACTURER_PART") "YAGEO    RC0603JR-07100R")
        (field (name "DB_APPROVED_BY") "ISHIDDEN=T")
      )
      (libsource (lib "Database_Libs1") (part "R"))
    )
    (comp (ref "R5")
      (value "10k")
      (footprint "SMD_0603_RESC1608X55N")
      (fields
        (field (name "DB_PART_NUMBER") "RES000008663")
        (field (name "DB_VALUE") "10k")
        (field (name "DB_TOLERANCE") "1%")
        (field (name "DB_MANUFACTURER_PART") "YAGEO    RC0603FR-0710KL")
        (field (name "DB_APPROVED_BY") "VSN")
      )
      (libsource (lib "Database_Libs1") (part "R"))
    )
    (comp (ref "R7")
      (value "100R")
      (footprint "SMD_0603_RESC1608X55N")
      (fields
        (field (name "DB_PART_NUMBER") "RES000006398")
        (field (name "DB_VALUE") "100R")
        (field (name "DB_TOLERANCE") "5%")
        (field (name "DB_MANUFACTURER_PART") "YAGEO    RC0603JR-07100R")
        (field (name "DB_APPROVED_BY") "ISHIDDEN=T")
      )
      (libsource (lib "Database_Libs1") (part "R"))
    )
    (comp (ref "R23")
      (value "10k")
      (footprint "SMD_0603_RESC1608X55N")
      (fields
        (field (name "DB_PART_NUMBER") "RES000008663")
        (field (name "DB_VALUE") "10k")
        (field (name "DB_TOLERANCE") "1%")
        (field (name "DB_MANUFACTURER_PART") "YAGEO    RC0603FR-0710KL")
        (field (name "DB_APPROVED_BY") "VSN")
      )
      (libsource (lib "Database_Libs1") (part "R"))
    )
    (comp (ref "R24")
      (value "100R")
      (footprint "SMD_0603_RESC1608X55N")
      (fields
        (field (name "DB_PART_NUMBER") "RES000006398")
        (field (name "DB_VALUE") "100R")
        (field (name "DB_TOLERANCE") "5%")
        (field (name "DB_MANUFACTURER_PART") "YAGEO    RC0603JR-07100R")
        (field (name "DB_APPROVED_BY") "ISHIDDEN=T")
      )
      (libsource (lib "Database_Libs1") (part "R"))
    )
    (comp (ref "TP4")
      (value "100_254")
      (footprint "SMD_TP_100-254")
      (fields
        (field (name "DB_PART_NUMBER") "TPO000000001")
        (field (name "DB_MANUFACTURER_PART") "ISHIDDEN=T")
        (field (name "DB_APPROVED_BY") "ISHIDDEN=T")
      )
      (libsource (lib "Database_Libs1") (part "TEST_POINT_1"))
    )
    (comp (ref "TP8")
      (value "100_254")
      (footprint "SMD_TP_100-254")
      (fields
        (field (name "DB_PART_NUMBER") "TPO000000001")
        (field (name "DB_MANUFACTURER_PART") "ISHIDDEN=T")
        (field (name "DB_APPROVED_BY") "ISHIDDEN=T")
      )
      (libsource (lib "Database_Libs1") (part "TEST_POINT_1"))
    )
    (comp (ref "TP15")
      (value "100_254")
      (footprint "SMD_TP_100-254")
      (fields
        (field (name "DB_PART_NUMBER") "TPO000000001")
        (field (name "DB_MANUFACTURER_PART") "ISHIDDEN=T")
        (field (name "DB_APPROVED_BY") "ISHIDDEN=T")
      )
      (libsource (lib "Database_Libs1") (part "TEST_POINT_1"))
    )
    (comp (ref "TP16")
      (value "100_254")
      (footprint "SMD_TP_100-254")
      (fields
        (field (name "DB_PART_NUMBER") "TPO000000001")
        (field (name "DB_MANUFACTURER_PART") "ISHIDDEN=T")
        (field (name "DB_APPROVED_BY") "ISHIDDEN=T")
      )
      (libsource (lib "Database_Libs1") (part "TEST_POINT_1"))
    )
    (comp (ref "TP27")
      (value "100_254")
      (footprint "SMD_TP_100-254")
      (fields
        (field (name "DB_PART_NUMBER") "TPO000000001")
        (field (name "DB_MANUFACTURER_PART") "ISHIDDEN=T")
        (field (name "DB_APPROVED_BY") "ISHIDDEN=T")
      )
      (libsource (lib "Database_Libs1") (part "TEST_POINT_1"))
    )
    (comp (ref "TP30")
      (value "100_254")
      (footprint "SMD_TP_100-254")
      (fields
        (field (name "DB_PART_NUMBER") "TPO000000001")
        (field (name "DB_MANUFACTURER_PART") "ISHIDDEN=T")
        (field (name "DB_APPROVED_BY") "ISHIDDEN=T")
      )
      (libsource (lib "Database_Libs1") (part "TEST_POINT_1"))
    )
    (comp (ref "TP31")
      (value "100_254")
      (footprint "SMD_TP_100-254")
      (fields
        (field (name "DB_PART_NUMBER") "TPO000000001")
        (field (name "DB_MANUFACTURER_PART") "ISHIDDEN=T")
        (field (name "DB_APPROVED_BY") "ISHIDDEN=T")
      )
      (libsource (lib "Database_Libs1") (part "TEST_POINT_1"))
    )
    (comp (ref "TP32")
      (value "100_254")
      (footprint "SMD_TP_100-254")
      (fields
        (field (name "DB_PART_NUMBER") "TPO000000001")
        (field (name "DB_MANUFACTURER_PART") "ISHIDDEN=T")
        (field (name "DB_APPROVED_BY") "ISHIDDEN=T")
      )
      (libsource (lib "Database_Libs1") (part "TEST_POINT_1"))
    )
    (comp (ref "U1")
      (value "~")
      (footprint "SMD_QFN50P600X600X80-43")
      (libsource (lib "BitCoin") (part "IC_SiC780"))
    )
    (comp (ref "U17")
      (value "~")
      (footprint "SMD_QFN50P600X600X80-43")
      (libsource (lib "BitCoin") (part "IC_SiC780"))
    )
    (comp (ref "U20")
      (value "~")
      (footprint "SMD_QFN50P600X600X80-43")
      (libsource (lib "BitCoin") (part "IC_SiC780"))
    )
    (comp (ref "U24")
      (value "~")
      (footprint "SMD_QFN50P600X600X80-43")
      (libsource (lib "BitCoin") (part "IC_SiC780"))
    )
  )
  (nets
    (net (code "1") (name "/1V") (class "Default")
      (node (ref "C128") (pin "1") (pinfunction "1_1") (pintype "passive"))
      (node (ref "C130") (pin "1") (pinfunction "1_1") (pintype "passive"))
      (node (ref "C131") (pin "1") (pinfunction "1_1") (pintype "passive"))
      (node (ref "C132") (pin "2") (pinfunction "2_2") (pintype "passive"))
      (node (ref "C138") (pin "1") (pinfunction "1_1") (pintype "passive"))
      (node (ref "C139") (pin "1") (pinfunction "1_1") (pintype "passive"))
      (node (ref "C140") (pin "2") (pinfunction "2_2") (pintype "passive"))
      (node (ref "C141") (pin "1") (pinfunction "1_1") (pintype "passive"))
      (node (ref "C170") (pin "1") (pinfunction "1_1") (pintype "passive"))
      (node (ref "C172") (pin "1") (pinfunction "1_1") (pintype "passive"))
      (node (ref "C173") (pin "1") (pinfunction "1_1") (pintype "passive"))
      (node (ref "C174") (pin "2") (pinfunction "2_2") (pintype "passive"))
      (node (ref "C175") (pin "1") (pinfunction "1_1") (pintype "passive"))
      (node (ref "C176") (pin "1") (pinfunction "1_1") (pintype "passive"))
      (node (ref "C187") (pin "1") (pinfunction "1_1") (pintype "passive"))
      (node (ref "C197") (pin "1") (pinfunction "1_1") (pintype "passive"))
      (node (ref "C199") (pin "1") (pinfunction "1_1") (pintype "passive"))
      (node (ref "C200") (pin "1") (pinfunction "1_1") (pintype "passive"))
      (node (ref "C202") (pin "1") (pinfunction "1_1") (pintype "passive"))
      (node (ref "C203") (pin "1") (pinfunction "1_1") (pintype "passive"))
      (node (ref "C205") (pin "1") (pinfunction "1_1") (pintype "passive"))
      (node (ref "C260") (pin "2") (pinfunction "2_2") (pintype "passive"))
      (node (ref "C261") (pin "2") (pinfunction "2_2") (pintype "passive"))
      (node (ref "C262") (pin "2") (pinfunction "2_2") (pintype "passive"))
      (node (ref "C263") (pin "1") (pinfunction "1_1") (pintype "passive"))
      (node (ref "C264") (pin "1") (pinfunction "1_1") (pintype "passive"))
      (node (ref "C265") (pin "1") (pinfunction "1_1") (pintype "passive"))
      (node (ref "C266") (pin "1") (pinfunction "1_1") (pintype "passive"))
      (node (ref "C267") (pin "2") (pinfunction "2_2") (pintype "passive"))
      (node (ref "C268") (pin "1") (pinfunction "1_1") (pintype "passive"))
      (node (ref "C269") (pin "1") (pinfunction "1_1") (pintype "passive"))
      (node (ref "C270") (pin "2") (pinfunction "2_2") (pintype "passive"))
      (node (ref "C271") (pin "1") (pinfunction "1_1") (pintype "passive"))
      (node (ref "C272") (pin "1") (pinfunction "1_1") (pintype "passive"))
      (node (ref "C273") (pin "2") (pinfunction "2_2") (pintype "passive"))
      (node (ref "C274") (pin "1") (pinfunction "1_1") (pintype "passive"))
      (node (ref "C275") (pin "1") (pinfunction "1_1") (pintype "passive"))
      (node (ref "C276") (pin "2") (pinfunction "2_2") (pintype "passive"))
      (node (ref "C33") (pin "1") (pinfunction "1_1") (pintype "passive"))
      (node (ref "C331") (pin "1") (pinfunction "1_1") (pintype "passive"))
      (node (ref "C332") (pin "1") (pinfunction "1_1") (pintype "passive"))
      (node (ref "C333") (pin "1") (pinfunction "1_1") (pintype "passive"))
      (node (ref "C334") (pin "1") (pinfunction "1_1") (pintype "passive"))
      (node (ref "C37") (pin "1") (pinfunction "1_1") (pintype "passive"))
      (node (ref "C375") (pin "2") (pinfunction "2_2") (pintype "passive"))
      (node (ref "C376") (pin "2") (pinfunction "2_2") (pintype "passive"))
      (node (ref "C377") (pin "2") (pinfunction "2_2") (pintype "passive"))
      (node (ref "C38") (pin "1") (pinfunction "1_1") (pintype "passive"))
      (node (ref "C381") (pin "2") (pinfunction "2_2") (pintype "passive"))
      (node (ref "C382") (pin "2") (pinfunction "2_2") (pintype "passive"))
      (node (ref "C39") (pin "1") (pinfunction "1_1") (pintype "passive"))
      (node (ref "C397") (pin "2") (pinfunction "2_2") (pintype "passive"))
      (node (ref "C398") (pin "2") (pinfunction "2_2") (pintype "passive"))
      (node (ref "C399") (pin "2") (pinfunction "2_2") (pintype "passive"))
      (node (ref "C40") (pin "1") (pinfunction "1_1") (pintype "passive"))
      (node (ref "C400") (pin "2") (pinfunction "2_2") (pintype "passive"))
      (node (ref "C401") (pin "2") (pinfunction "2_2") (pintype "passive"))
      (node (ref "C65") (pin "1") (pinfunction "1_1") (pintype "passive"))
      (node (ref "C652") (pin "1") (pinfunction "1_1") (pintype "passive"))
      (node (ref "C653") (pin "2") (pinfunction "2_2") (pintype "passive"))
      (node (ref "C654") (pin "1") (pinfunction "1_1") (pintype "passive"))
      (node (ref "C655") (pin "1") (pinfunction "1_1") (pintype "passive"))
      (node (ref "C656") (pin "2") (pinfunction "2_2") (pintype "passive"))
      (node (ref "C657") (pin "1") (pinfunction "1_1") (pintype "passive"))
      (node (ref "C658") (pin "1") (pinfunction "1_1") (pintype "passive"))
      (node (ref "C659") (pin "2") (pinfunction "2_2") (pintype "passive"))
      (node (ref "C66") (pin "1") (pinfunction "1_1") (pintype "passive"))
      (node (ref "C660") (pin "1") (pinfunction "1_1") (pintype "passive"))
      (node (ref "C67") (pin "1") (pinfunction "1_1") (pintype "passive"))
      (node (ref "L10") (pin "2") (pinfunction "2_2") (pintype "passive"))
      (node (ref "L14") (pin "2") (pinfunction "2_2") (pintype "passive"))
      (node (ref "L3") (pin "2") (pinfunction "2_2") (pintype "passive"))
      (node (ref "L7") (pin "2") (pinfunction "2_2") (pintype "passive"))
    )
    (net (code "2") (name "/5.0V") (class "Default")
      (node (ref "C117") (pin "2") (pinfunction "2_2") (pintype "passive"))
      (node (ref "C22") (pin "2") (pinfunction "2_2") (pintype "passive"))
      (node (ref "C54") (pin "2") (pinfunction "2_2") (pintype "passive"))
      (node (ref "C85") (pin "2") (pinfunction "2_2") (pintype "passive"))
      (node (ref "R1") (pin "2") (pinfunction "2_2") (pintype "passive"))
      (node (ref "R2") (pin "2") (pinfunction "2_2") (pintype "passive"))
      (node (ref "R23") (pin "2") (pinfunction "2_2") (pintype "passive"))
      (node (ref "R24") (pin "1") (pinfunction "1_1") (pintype "passive"))
      (node (ref "R3") (pin "1") (pinfunction "1_1") (pintype "passive"))
      (node (ref "R4") (pin "1") (pinfunction "1_1") (pintype "passive"))
      (node (ref "R5") (pin "2") (pinfunction "2_2") (pintype "passive"))
      (node (ref "R7") (pin "1") (pinfunction "1_1") (pintype "passive"))
      (node (ref "U1") (pin "3") (pinfunction "VDRV_3") (pintype "passive"))
      (node (ref "U17") (pin "3") (pinfunction "VDRV_3") (pintype "passive"))
      (node (ref "U20") (pin "3") (pinfunction "VDRV_3") (pintype "passive"))
      (node (ref "U24") (pin "3") (pinfunction "VDRV_3") (pintype "passive"))
    )
    (net (code "3") (name "/12V") (class "Default")
      (node (ref "C100") (pin "1") (pinfunction "1_1") (pintype "passive"))
      (node (ref "C101") (pin "2") (pinfunction "2_2") (pintype "passive"))
      (node (ref "C102") (pin "2") (pinfunction "2_2") (pintype "passive"))
      (node (ref "C108") (pin "1") (pinfunction "1_1") (pintype "passive"))
      (node (ref "C109") (pin "1") (pinfunction "1_1") (pintype "passive"))
      (node (ref "C110") (pin "1") (pinfunction "1_1") (pintype "passive"))
      (node (ref "C111") (pin "1") (pinfunction "1_1") (pintype "passive"))
      (node (ref "C112") (pin "1") (pinfunction "1_1") (pintype "passive"))
      (node (ref "C113") (pin "1") (pinfunction "1_1") (pintype "passive"))
      (node (ref "C114") (pin "1") (pinfunction "1_1") (pintype "passive"))
      (node (ref "C115") (pin "1") (pinfunction "1_1") (pintype "passive"))
      (node (ref "C116") (pin "1") (pinfunction "1_1") (pintype "passive"))
      (node (ref "C118") (pin "1") (pinfunction "1_1") (pintype "passive"))
      (node (ref "C119") (pin "1") (pinfunction "1_1") (pintype "passive"))
      (node (ref "C120") (pin "1") (pinfunction "1_1") (pintype "passive"))
      (node (ref "C122") (pin "1") (pinfunction "1_1") (pintype "passive"))
      (node (ref "C123") (pin "1") (pinfunction "1_1") (pintype "passive"))
      (node (ref "C124") (pin "1") (pinfunction "1_1") (pintype "passive"))
      (node (ref "C126") (pin "1") (pinfunction "1_1") (pintype "passive"))
      (node (ref "C127") (pin "1") (pinfunction "1_1") (pintype "passive"))
      (node (ref "C133") (pin "2") (pinfunction "2_2") (pintype "passive"))
      (node (ref "C134") (pin "2") (pinfunction "2_2") (pintype "passive"))
      (node (ref "C20") (pin "1") (pinfunction "1_1") (pintype "passive"))
      (node (ref "C21") (pin "1") (pinfunction "1_1") (pintype "passive"))
      (node (ref "C23") (pin "1") (pinfunction "1_1") (pintype "passive"))
      (node (ref "C24") (pin "1") (pinfunction "1_1") (pintype "passive"))
      (node (ref "C25") (pin "1") (pinfunction "1_1") (pintype "passive"))
      (node (ref "C258") (pin "2") (pinfunction "2_2") (pintype "passive"))
      (node (ref "C259") (pin "2") (pinfunction "2_2") (pintype "passive"))
      (node (ref "C27") (pin "1") (pinfunction "1_1") (pintype "passive"))
      (node (ref "C28") (pin "1") (pinfunction "1_1") (pintype "passive"))
      (node (ref "C29") (pin "1") (pinfunction "1_1") (pintype "passive"))
      (node (ref "C31") (pin "1") (pinfunction "1_1") (pintype "passive"))
      (node (ref "C32") (pin "2") (pinfunction "2_2") (pintype "passive"))
      (node (ref "C373") (pin "2") (pinfunction "2_2") (pintype "passive"))
      (node (ref "C374") (pin "2") (pinfunction "2_2") (pintype "passive"))
      (node (ref "C378") (pin "1") (pinfunction "1_1") (pintype "passive"))
      (node (ref "C379") (pin "1") (pinfunction "1_1") (pintype "passive"))
      (node (ref "C380") (pin "1") (pinfunction "1_1") (pintype "passive"))
      (node (ref "C404") (pin "2") (pinfunction "2_2") (pintype "passive"))
      (node (ref "C405") (pin "2") (pinfunction "2_2") (pintype "passive"))
      (node (ref "C406") (pin "2") (pinfunction "2_2") (pintype "passive"))
      (node (ref "C407") (pin "2") (pinfunction "2_2") (pintype "passive"))
      (node (ref "C41") (pin "2") (pinfunction "2_2") (pintype "passive"))
      (node (ref "C42") (pin "2") (pinfunction "2_2") (pintype "passive"))
      (node (ref "C43") (pin "2") (pinfunction "2_2") (pintype "passive"))
      (node (ref "C47") (pin "2") (pinfunction "2_2") (pintype "passive"))
      (node (ref "C49") (pin "1") (pinfunction "1_1") (pintype "passive"))
      (node (ref "C50") (pin "1") (pinfunction "1_1") (pintype "passive"))
      (node (ref "C51") (pin "1") (pinfunction "1_1") (pintype "passive"))
      (node (ref "C52") (pin "1") (pinfunction "1_1") (pintype "passive"))
      (node (ref "C596") (pin "2") (pinfunction "2_2") (pintype "passive"))
      (node (ref "C598") (pin "1") (pinfunction "1_1") (pintype "passive"))
      (node (ref "C599") (pin "2") (pinfunction "2_2") (pintype "passive"))
      (node (ref "C600") (pin "1") (pinfunction "1_1") (pintype "passive"))
      (node (ref "C602") (pin "2") (pinfunction "2_2") (pintype "passive"))
      (node (ref "C603") (pin "1") (pinfunction "1_1") (pintype "passive"))
      (node (ref "C605") (pin "2") (pinfunction "2_2") (pintype "passive"))
      (node (ref "C606") (pin "1") (pinfunction "1_1") (pintype "passive"))
      (node (ref "C640") (pin "1") (pinfunction "1_1") (pintype "passive"))
      (node (ref "C642") (pin "1") (pinfunction "1_1") (pintype "passive"))
      (node (ref "C68") (pin "1") (pinfunction "1_1") (pintype "passive"))
      (node (ref "C69") (pin "1") (pinfunction "1_1") (pintype "passive"))
      (node (ref "C70") (pin "1") (pinfunction "1_1") (pintype "passive"))
      (node (ref "C71") (pin "1") (pinfunction "1_1") (pintype "passive"))
      (node (ref "C711") (pin "1") (pinfunction "1_1") (pintype "passive"))
      (node (ref "C814") (pin "1") (pinfunction "1_1") (pintype "passive"))
      (node (ref "C92") (pin "2") (pinfunction "2_2") (pintype "passive"))
      (node (ref "C96") (pin "2") (pinfunction "2_2") (pintype "passive"))
      (node (ref "C97") (pin "1") (pinfunction "1_1") (pintype "passive"))
      (node (ref "C98") (pin "1") (pinfunction "1_1") (pintype "passive"))
      (node (ref "C99") (pin "2") (pinfunction "2_2") (pintype "passive"))
      (node (ref "U1") (pin "10") (pinfunction "VIN_10") (pintype "passive"))
      (node (ref "U1") (pin "11") (pinfunction "VIN_11") (pintype "passive"))
      (node (ref "U1") (pin "12") (pinfunction "VIN_12") (pintype "passive"))
      (node (ref "U1") (pin "13") (pinfunction "VIN_13") (pintype "passive"))
      (node (ref "U1") (pin "14") (pinfunction "VIN_14") (pintype "passive"))
      (node (ref "U1") (pin "42") (pinfunction "VIN_42") (pintype "passive"))
      (node (ref "U1") (pin "8") (pinfunction "VIN_8") (pintype "passive"))
      (node (ref "U1") (pin "9") (pinfunction "VIN_9") (pintype "passive"))
      (node (ref "U17") (pin "10") (pinfunction "VIN_10") (pintype "passive"))
      (node (ref "U17") (pin "11") (pinfunction "VIN_11") (pintype "passive"))
      (node (ref "U17") (pin "12") (pinfunction "VIN_12") (pintype "passive"))
      (node (ref "U17") (pin "13") (pinfunction "VIN_13") (pintype "passive"))
      (node (ref "U17") (pin "14") (pinfunction "VIN_14") (pintype "passive"))
      (node (ref "U17") (pin "42") (pinfunction "VIN_42") (pintype "passive"))
      (node (ref "U17") (pin "8") (pinfunction "VIN_8") (pintype "passive"))
      (node (ref "U17") (pin "9") (pinfunction "VIN_9") (pintype "passive"))
      (node (ref "U20") (pin "10") (pinfunction "VIN_10") (pintype "passive"))
      (node (ref "U20") (pin "11") (pinfunction "VIN_11") (pintype "passive"))
      (node (ref "U20") (pin "12") (pinfunction "VIN_12") (pintype "passive"))
      (node (ref "U20") (pin "13") (pinfunction "VIN_13") (pintype "passive"))
      (node (ref "U20") (pin "14") (pinfunction "VIN_14") (pintype "passive"))
      (node (ref "U20") (pin "42") (pinfunction "VIN_42") (pintype "passive"))
      (node (ref "U20") (pin "8") (pinfunction "VIN_8") (pintype "passive"))
      (node (ref "U20") (pin "9") (pinfunction "VIN_9") (pintype "passive"))
      (node (ref "U24") (pin "10") (pinfunction "VIN_10") (pintype "passive"))
      (node (ref "U24") (pin "11") (pinfunction "VIN_11") (pintype "passive"))
      (node (ref "U24") (pin "12") (pinfunction "VIN_12") (pintype "passive"))
      (node (ref "U24") (pin "13") (pinfunction "VIN_13") (pintype "passive"))
      (node (ref "U24") (pin "14") (pinfunction "VIN_14") (pintype "passive"))
      (node (ref "U24") (pin "42") (pinfunction "VIN_42") (pintype "passive"))
      (node (ref "U24") (pin "8") (pinfunction "VIN_8") (pintype "passive"))
      (node (ref "U24") (pin "9") (pinfunction "VIN_9") (pintype "passive"))
    )
    (net (code "4") (name "/PWM1L") (class "Default")
      (node (ref "U1") (pin "40") (pinfunction "PWM_40") (pintype "passive"))
    )
    (net (code "5") (name "/PWM2L") (class "Default")
      (node (ref "U17") (pin "40") (pinfunction "PWM_40") (pintype "passive"))
    )
    (net (code "6") (name "/PWM3H") (class "Default")
      (node (ref "U20") (pin "40") (pinfunction "PWM_40") (pintype "passive"))
    )
    (net (code "7") (name "/PWM4H") (class "Default")
      (node (ref "U24") (pin "40") (pinfunction "PWM_40") (pintype "passive"))
    )
    (net (code "8") (name "/SWN7") (class "Default")
      (node (ref "L10") (pin "1") (pinfunction "1_1") (pintype "passive"))
      (node (ref "U20") (pin "15") (pinfunction "VSWH_15") (pintype "passive"))
      (node (ref "U20") (pin "29") (pinfunction "VSWH_29") (pintype "passive"))
      (node (ref "U20") (pin "30") (pinfunction "VSWH_30") (pintype "passive"))
      (node (ref "U20") (pin "31") (pinfunction "VSWH_31") (pintype "passive"))
      (node (ref "U20") (pin "32") (pinfunction "VSWH_32") (pintype "passive"))
      (node (ref "U20") (pin "33") (pinfunction "VSWH_33") (pintype "passive"))
      (node (ref "U20") (pin "34") (pinfunction "VSWH_34") (pintype "passive"))
      (node (ref "U20") (pin "35") (pinfunction "VSWH_35") (pintype "passive"))
      (node (ref "U20") (pin "43") (pinfunction "VSWH_43") (pintype "passive"))
    )
    (net (code "9") (name "/SWN8") (class "Default")
      (node (ref "L14") (pin "1") (pinfunction "1_1") (pintype "passive"))
      (node (ref "U24") (pin "15") (pinfunction "VSWH_15") (pintype "passive"))
      (node (ref "U24") (pin "29") (pinfunction "VSWH_29") (pintype "passive"))
      (node (ref "U24") (pin "30") (pinfunction "VSWH_30") (pintype "passive"))
      (node (ref "U24") (pin "31") (pinfunction "VSWH_31") (pintype "passive"))
      (node (ref "U24") (pin "32") (pinfunction "VSWH_32") (pintype "passive"))
      (node (ref "U24") (pin "33") (pinfunction "VSWH_33") (pintype "passive"))
      (node (ref "U24") (pin "34") (pinfunction "VSWH_34") (pintype "passive"))
      (node (ref "U24") (pin "35") (pinfunction "VSWH_35") (pintype "passive"))
      (node (ref "U24") (pin "43") (pinfunction "VSWH_43") (pintype "passive"))
    )
    (net (code "10") (name "/SWN9") (class "Default")
      (node (ref "L3") (pin "1") (pinfunction "1_1") (pintype "passive"))
      (node (ref "U1") (pin "15") (pinfunction "VSWH_15") (pintype "passive"))
      (node (ref "U1") (pin "29") (pinfunction "VSWH_29") (pintype "passive"))
      (node (ref "U1") (pin "30") (pinfunction "VSWH_30") (pintype "passive"))
      (node (ref "U1") (pin "31") (pinfunction "VSWH_31") (pintype "passive"))
      (node (ref "U1") (pin "32") (pinfunction "VSWH_32") (pintype "passive"))
      (node (ref "U1") (pin "33") (pinfunction "VSWH_33") (pintype "passive"))
      (node (ref "U1") (pin "34") (pinfunction "VSWH_34") (pintype "passive"))
      (node (ref "U1") (pin "35") (pinfunction "VSWH_35") (pintype "passive"))
      (node (ref "U1") (pin "43") (pinfunction "VSWH_43") (pintype "passive"))
    )
    (net (code "11") (name "/SWN10") (class "Default")
      (node (ref "L7") (pin "1") (pinfunction "1_1") (pintype "passive"))
      (node (ref "U17") (pin "15") (pinfunction "VSWH_15") (pintype "passive"))
      (node (ref "U17") (pin "29") (pinfunction "VSWH_29") (pintype "passive"))
      (node (ref "U17") (pin "30") (pinfunction "VSWH_30") (pintype "passive"))
      (node (ref "U17") (pin "31") (pinfunction "VSWH_31") (pintype "passive"))
      (node (ref "U17") (pin "32") (pinfunction "VSWH_32") (pintype "passive"))
      (node (ref "U17") (pin "33") (pinfunction "VSWH_33") (pintype "passive"))
      (node (ref "U17") (pin "34") (pinfunction "VSWH_34") (pintype "passive"))
      (node (ref "U17") (pin "35") (pinfunction "VSWH_35") (pintype "passive"))
      (node (ref "U17") (pin "43") (pinfunction "VSWH_43") (pintype "passive"))
    )
    (net (code "12") (name "/THDN") (class "Default")
      (node (ref "U1") (pin "38") (pinfunction "THDN_38") (pintype "passive"))
      (node (ref "U17") (pin "38") (pinfunction "THDN_38") (pintype "passive"))
      (node (ref "U20") (pin "38") (pinfunction "THDN_38") (pintype "passive"))
      (node (ref "U24") (pin "38") (pinfunction "THDN_38") (pintype "passive"))
    )
    (net (code "13") (name "GND") (class "Default")
      (node (ref "C100") (pin "2") (pinfunction "2_2") (pintype "passive"))
      (node (ref "C101") (pin "1") (pinfunction "1_1") (pintype "passive"))
      (node (ref "C102") (pin "1") (pinfunction "1_1") (pintype "passive"))
      (node (ref "C108") (pin "2") (pinfunction "2_2") (pintype "passive"))
      (node (ref "C109") (pin "2") (pinfunction "2_2") (pintype "passive"))
      (node (ref "C110") (pin "2") (pinfunction "2_2") (pintype "passive"))
      (node (ref "C111") (pin "2") (pinfunction "2_2") (pintype "passive"))
      (node (ref "C112") (pin "2") (pinfunction "2_2") (pintype "passive"))
      (node (ref "C113") (pin "2") (pinfunction "2_2") (pintype "passive"))
      (node (ref "C114") (pin "2") (pinfunction "2_2") (pintype "passive"))
      (node (ref "C115") (pin "2") (pinfunction "2_2") (pintype "passive"))
      (node (ref "C116") (pin "2") (pinfunction "2_2") (pintype "passive"))
      (node (ref "C117") (pin "1") (pinfunction "1_1") (pintype "passive"))
      (node (ref "C118") (pin "2") (pinfunction "2_2") (pintype "passive"))
      (node (ref "C119") (pin "2") (pinfunction "2_2") (pintype "passive"))
      (node (ref "C120") (pin "2") (pinfunction "2_2") (pintype "passive"))
      (node (ref "C121") (pin "2") (pinfunction "2_2") (pintype "passive"))
      (node (ref "C122") (pin "2") (pinfunction "2_2") (pintype "passive"))
      (node (ref "C123") (pin "2") (pinfunction "2_2") (pintype "passive"))
      (node (ref "C124") (pin "2") (pinfunction "2_2") (pintype "passive"))
      (node (ref "C126") (pin "2") (pinfunction "2_2") (pintype "passive"))
      (node (ref "C127") (pin "2") (pinfunction "2_2") (pintype "passive"))
      (node (ref "C128") (pin "2") (pinfunction "2_2") (pintype "passive"))
      (node (ref "C130") (pin "2") (pinfunction "2_2") (pintype "passive"))
      (node (ref "C131") (pin "2") (pinfunction "2_2") (pintype "passive"))
      (node (ref "C132") (pin "1") (pinfunction "1_1") (pintype "passive"))
      (node (ref "C133") (pin "1") (pinfunction "1_1") (pintype "passive"))
      (node (ref "C134") (pin "1") (pinfunction "1_1") (pintype "passive"))
      (node (ref "C138") (pin "2") (pinfunction "2_2") (pintype "passive"))
      (node (ref "C139") (pin "2") (pinfunction "2_2") (pintype "passive"))
      (node (ref "C140") (pin "1") (pinfunction "1_1") (pintype "passive"))
      (node (ref "C141") (pin "2") (pinfunction "2_2") (pintype "passive"))
      (node (ref "C170") (pin "2") (pinfunction "2_2") (pintype "passive"))
      (node (ref "C172") (pin "2") (pinfunction "2_2") (pintype "passive"))
      (node (ref "C173") (pin "2") (pinfunction "2_2") (pintype "passive"))
      (node (ref "C174") (pin "1") (pinfunction "1_1") (pintype "passive"))
      (node (ref "C175") (pin "2") (pinfunction "2_2") (pintype "passive"))
      (node (ref "C176") (pin "2") (pinfunction "2_2") (pintype "passive"))
      (node (ref "C187") (pin "2") (pinfunction "2_2") (pintype "passive"))
      (node (ref "C197") (pin "2") (pinfunction "2_2") (pintype "passive"))
      (node (ref "C199") (pin "2") (pinfunction "2_2") (pintype "passive"))
      (node (ref "C20") (pin "2") (pinfunction "2_2") (pintype "passive"))
      (node (ref "C200") (pin "2") (pinfunction "2_2") (pintype "passive"))
      (node (ref "C202") (pin "2") (pinfunction "2_2") (pintype "passive"))
      (node (ref "C203") (pin "2") (pinfunction "2_2") (pintype "passive"))
      (node (ref "C205") (pin "2") (pinfunction "2_2") (pintype "passive"))
      (node (ref "C21") (pin "2") (pinfunction "2_2") (pintype "passive"))
      (node (ref "C22") (pin "1") (pinfunction "1_1") (pintype "passive"))
      (node (ref "C23") (pin "2") (pinfunction "2_2") (pintype "passive"))
      (node (ref "C24") (pin "2") (pinfunction "2_2") (pintype "passive"))
      (node (ref "C25") (pin "2") (pinfunction "2_2") (pintype "passive"))
      (node (ref "C258") (pin "1") (pinfunction "1_1") (pintype "passive"))
      (node (ref "C259") (pin "1") (pinfunction "1_1") (pintype "passive"))
      (node (ref "C26") (pin "2") (pinfunction "2_2") (pintype "passive"))
      (node (ref "C260") (pin "1") (pinfunction "1_1") (pintype "passive"))
      (node (ref "C261") (pin "1") (pinfunction "1_1") (pintype "passive"))
      (node (ref "C262") (pin "1") (pinfunction "1_1") (pintype "passive"))
      (node (ref "C263") (pin "2") (pinfunction "2_2") (pintype "passive"))
      (node (ref "C264") (pin "2") (pinfunction "2_2") (pintype "passive"))
      (node (ref "C265") (pin "2") (pinfunction "2_2") (pintype "passive"))
      (node (ref "C266") (pin "2") (pinfunction "2_2") (pintype "passive"))
      (node (ref "C267") (pin "1") (pinfunction "1_1") (pintype "passive"))
      (node (ref "C268") (pin "2") (pinfunction "2_2") (pintype "passive"))
      (node (ref "C269") (pin "2") (pinfunction "2_2") (pintype "passive"))
      (node (ref "C27") (pin "2") (pinfunction "2_2") (pintype "passive"))
      (node (ref "C270") (pin "1") (pinfunction "1_1") (pintype "passive"))
      (node (ref "C271") (pin "2") (pinfunction "2_2") (pintype "passive"))
      (node (ref "C272") (pin "2") (pinfunction "2_2") (pintype "passive"))
      (node (ref "C273") (pin "1") (pinfunction "1_1") (pintype "passive"))
      (node (ref "C274") (pin "2") (pinfunction "2_2") (pintype "passive"))
      (node (ref "C275") (pin "2") (pinfunction "2_2") (pintype "passive"))
      (node (ref "C276") (pin "1") (pinfunction "1_1") (pintype "passive"))
      (node (ref "C28") (pin "2") (pinfunction "2_2") (pintype "passive"))
      (node (ref "C29") (pin "2") (pinfunction "2_2") (pintype "passive"))
      (node (ref "C31") (pin "2") (pinfunction "2_2") (pintype "passive"))
      (node (ref "C32") (pin "1") (pinfunction "1_1") (pintype "passive"))
      (node (ref "C33") (pin "2") (pinfunction "2_2") (pintype "passive"))
      (node (ref "C331") (pin "2") (pinfunction "2_2") (pintype "passive"))
      (node (ref "C332") (pin "2") (pinfunction "2_2") (pintype "passive"))
      (node (ref "C333") (pin "2") (pinfunction "2_2") (pintype "passive"))
      (node (ref "C334") (pin "2") (pinfunction "2_2") (pintype "passive"))
      (node (ref "C37") (pin "2") (pinfunction "2_2") (pintype "passive"))
      (node (ref "C373") (pin "1") (pinfunction "1_1") (pintype "passive"))
      (node (ref "C374") (pin "1") (pinfunction "1_1") (pintype "passive"))
      (node (ref "C375") (pin "1") (pinfunction "1_1") (pintype "passive"))
      (node (ref "C376") (pin "1") (pinfunction "1_1") (pintype "passive"))
      (node (ref "C377") (pin "1") (pinfunction "1_1") (pintype "passive"))
      (node (ref "C378") (pin "2") (pinfunction "2_2") (pintype "passive"))
      (node (ref "C379") (pin "2") (pinfunction "2_2") (pintype "passive"))
      (node (ref "C38") (pin "2") (pinfunction "2_2") (pintype "passive"))
      (node (ref "C380") (pin "2") (pinfunction "2_2") (pintype "passive"))
      (node (ref "C381") (pin "1") (pinfunction "1_1") (pintype "passive"))
      (node (ref "C382") (pin "1") (pinfunction "1_1") (pintype "passive"))
      (node (ref "C39") (pin "2") (pinfunction "2_2") (pintype "passive"))
      (node (ref "C397") (pin "1") (pinfunction "1_1") (pintype "passive"))
      (node (ref "C398") (pin "1") (pinfunction "1_1") (pintype "passive"))
      (node (ref "C399") (pin "1") (pinfunction "1_1") (pintype "passive"))
      (node (ref "C40") (pin "2") (pinfunction "2_2") (pintype "passive"))
      (node (ref "C400") (pin "1") (pinfunction "1_1") (pintype "passive"))
      (node (ref "C401") (pin "1") (pinfunction "1_1") (pintype "passive"))
      (node (ref "C404") (pin "1") (pinfunction "1_1") (pintype "passive"))
      (node (ref "C405") (pin "1") (pinfunction "1_1") (pintype "passive"))
      (node (ref "C406") (pin "1") (pinfunction "1_1") (pintype "passive"))
      (node (ref "C407") (pin "1") (pinfunction "1_1") (pintype "passive"))
      (node (ref "C41") (pin "1") (pinfunction "1_1") (pintype "passive"))
      (node (ref "C42") (pin "1") (pinfunction "1_1") (pintype "passive"))
      (node (ref "C43") (pin "1") (pinfunction "1_1") (pintype "passive"))
      (node (ref "C47") (pin "1") (pinfunction "1_1") (pintype "passive"))
      (node (ref "C49") (pin "2") (pinfunction "2_2") (pintype "passive"))
      (node (ref "C50") (pin "2") (pinfunction "2_2") (pintype "passive"))
      (node (ref "C51") (pin "2") (pinfunction "2_2") (pintype "passive"))
      (node (ref "C52") (pin "2") (pinfunction "2_2") (pintype "passive"))
      (node (ref "C54") (pin "1") (pinfunction "1_1") (pintype "passive"))
      (node (ref "C58") (pin "2") (pinfunction "2_2") (pintype "passive"))
      (node (ref "C596") (pin "1") (pinfunction "1_1") (pintype "passive"))
      (node (ref "C598") (pin "2") (pinfunction "2_2") (pintype "passive"))
      (node (ref "C599") (pin "1") (pinfunction "1_1") (pintype "passive"))
      (node (ref "C600") (pin "2") (pinfunction "2_2") (pintype "passive"))
      (node (ref "C602") (pin "1") (pinfunction "1_1") (pintype "passive"))
      (node (ref "C603") (pin "2") (pinfunction "2_2") (pintype "passive"))
      (node (ref "C605") (pin "1") (pinfunction "1_1") (pintype "passive"))
      (node (ref "C606") (pin "2") (pinfunction "2_2") (pintype "passive"))
      (node (ref "C640") (pin "2") (pinfunction "2_2") (pintype "passive"))
      (node (ref "C642") (pin "2") (pinfunction "2_2") (pintype "passive"))
      (node (ref "C65") (pin "2") (pinfunction "2_2") (pintype "passive"))
      (node (ref "C652") (pin "2") (pinfunction "2_2") (pintype "passive"))
      (node (ref "C653") (pin "1") (pinfunction "1_1") (pintype "passive"))
      (node (ref "C654") (pin "2") (pinfunction "2_2") (pintype "passive"))
      (node (ref "C655") (pin "2") (pinfunction "2_2") (pintype "passive"))
      (node (ref "C656") (pin "1") (pinfunction "1_1") (pintype "passive"))
      (node (ref "C657") (pin "2") (pinfunction "2_2") (pintype "passive"))
      (node (ref "C658") (pin "2") (pinfunction "2_2") (pintype "passive"))
      (node (ref "C659") (pin "1") (pinfunction "1_1") (pintype "passive"))
      (node (ref "C66") (pin "2") (pinfunction "2_2") (pintype "passive"))
      (node (ref "C660") (pin "2") (pinfunction "2_2") (pintype "passive"))
      (node (ref "C67") (pin "2") (pinfunction "2_2") (pintype "passive"))
      (node (ref "C68") (pin "2") (pinfunction "2_2") (pintype "passive"))
      (node (ref "C69") (pin "2") (pinfunction "2_2") (pintype "passive"))
      (node (ref "C70") (pin "2") (pinfunction "2_2") (pintype "passive"))
      (node (ref "C71") (pin "2") (pinfunction "2_2") (pintype "passive"))
      (node (ref "C711") (pin "2") (pinfunction "2_2") (pintype "passive"))
      (node (ref "C814") (pin "2") (pinfunction "2_2") (pintype "passive"))
      (node (ref "C85") (pin "1") (pinfunction "1_1") (pintype "passive"))
      (node (ref "C89") (pin "2") (pinfunction "2_2") (pintype "passive"))
      (node (ref "C92") (pin "1") (pinfunction "1_1") (pintype "passive"))
      (node (ref "C96") (pin "1") (pinfunction "1_1") (pintype "passive"))
      (node (ref "C97") (pin "2") (pinfunction "2_2") (pintype "passive"))
      (node (ref "C98") (pin "2") (pinfunction "2_2") (pintype "passive"))
      (node (ref "C99") (pin "1") (pinfunction "1_1") (pintype "passive"))
      (node (ref "U1") (pin "16") (pinfunction "PGND_16") (pintype "passive"))
      (node (ref "U1") (pin "17") (pinfunction "PGND_17") (pintype "passive"))
      (node (ref "U1") (pin "18") (pinfunction "PGND_18") (pintype "passive"))
      (node (ref "U1") (pin "19") (pinfunction "PGND_19") (pintype "passive"))
      (node (ref "U1") (pin "20") (pinfunction "PGND_20") (pintype "passive"))
      (node (ref "U1") (pin "21") (pinfunction "PGND_21") (pintype "passive"))
      (node (ref "U1") (pin "22") (pinfunction "PGND_22") (pintype "passive"))
      (node (ref "U1") (pin "23") (pinfunction "PGND_23") (pintype "passive"))
      (node (ref "U1") (pin "24") (pinfunction "PGND_24") (pintype "passive"))
      (node (ref "U1") (pin "25") (pinfunction "PGND_25") (pintype "passive"))
      (node (ref "U1") (pin "26") (pinfunction "PGND_26") (pintype "passive"))
      (node (ref "U1") (pin "27") (pinfunction "PGND_27") (pintype "passive"))
      (node (ref "U1") (pin "28") (pinfunction "PGND_28") (pintype "passive"))
      (node (ref "U1") (pin "37") (pinfunction "CGND_37") (pintype "passive"))
      (node (ref "U1") (pin "41") (pinfunction "CGND_41") (pintype "passive"))
      (node (ref "U1") (pin "5") (pinfunction "CGND_5") (pintype "passive"))
      (node (ref "U17") (pin "16") (pinfunction "PGND_16") (pintype "passive"))
      (node (ref "U17") (pin "17") (pinfunction "PGND_17") (pintype "passive"))
      (node (ref "U17") (pin "18") (pinfunction "PGND_18") (pintype "passive"))
      (node (ref "U17") (pin "19") (pinfunction "PGND_19") (pintype "passive"))
      (node (ref "U17") (pin "20") (pinfunction "PGND_20") (pintype "passive"))
      (node (ref "U17") (pin "21") (pinfunction "PGND_21") (pintype "passive"))
      (node (ref "U17") (pin "22") (pinfunction "PGND_22") (pintype "passive"))
      (node (ref "U17") (pin "23") (pinfunction "PGND_23") (pintype "passive"))
      (node (ref "U17") (pin "24") (pinfunction "PGND_24") (pintype "passive"))
      (node (ref "U17") (pin "25") (pinfunction "PGND_25") (pintype "passive"))
      (node (ref "U17") (pin "26") (pinfunction "PGND_26") (pintype "passive"))
      (node (ref "U17") (pin "27") (pinfunction "PGND_27") (pintype "passive"))
      (node (ref "U17") (pin "28") (pinfunction "PGND_28") (pintype "passive"))
      (node (ref "U17") (pin "37") (pinfunction "CGND_37") (pintype "passive"))
      (node (ref "U17") (pin "41") (pinfunction "CGND_41") (pintype "passive"))
      (node (ref "U17") (pin "5") (pinfunction "CGND_5") (pintype "passive"))
      (node (ref "U20") (pin "16") (pinfunction "PGND_16") (pintype "passive"))
      (node (ref "U20") (pin "17") (pinfunction "PGND_17") (pintype "passive"))
      (node (ref "U20") (pin "18") (pinfunction "PGND_18") (pintype "passive"))
      (node (ref "U20") (pin "19") (pinfunction "PGND_19") (pintype "passive"))
      (node (ref "U20") (pin "20") (pinfunction "PGND_20") (pintype "passive"))
      (node (ref "U20") (pin "21") (pinfunction "PGND_21") (pintype "passive"))
      (node (ref "U20") (pin "22") (pinfunction "PGND_22") (pintype "passive"))
      (node (ref "U20") (pin "23") (pinfunction "PGND_23") (pintype "passive"))
      (node (ref "U20") (pin "24") (pinfunction "PGND_24") (pintype "passive"))
      (node (ref "U20") (pin "25") (pinfunction "PGND_25") (pintype "passive"))
      (node (ref "U20") (pin "26") (pinfunction "PGND_26") (pintype "passive"))
      (node (ref "U20") (pin "27") (pinfunction "PGND_27") (pintype "passive"))
      (node (ref "U20") (pin "28") (pinfunction "PGND_28") (pintype "passive"))
      (node (ref "U20") (pin "37") (pinfunction "CGND_37") (pintype "passive"))
      (node (ref "U20") (pin "41") (pinfunction "CGND_41") (pintype "passive"))
      (node (ref "U20") (pin "5") (pinfunction "CGND_5") (pintype "passive"))
      (node (ref "U24") (pin "16") (pinfunction "PGND_16") (pintype "passive"))
      (node (ref "U24") (pin "17") (pinfunction "PGND_17") (pintype "passive"))
      (node (ref "U24") (pin "18") (pinfunction "PGND_18") (pintype "passive"))
      (node (ref "U24") (pin "19") (pinfunction "PGND_19") (pintype "passive"))
      (node (ref "U24") (pin "20") (pinfunction "PGND_20") (pintype "passive"))
      (node (ref "U24") (pin "21") (pinfunction "PGND_21") (pintype "passive"))
      (node (ref "U24") (pin "22") (pinfunction "PGND_22") (pintype "passive"))
      (node (ref "U24") (pin "23") (pinfunction "PGND_23") (pintype "passive"))
      (node (ref "U24") (pin "24") (pinfunction "PGND_24") (pintype "passive"))
      (node (ref "U24") (pin "25") (pinfunction "PGND_25") (pintype "passive"))
      (node (ref "U24") (pin "26") (pinfunction "PGND_26") (pintype "passive"))
      (node (ref "U24") (pin "27") (pinfunction "PGND_27") (pintype "passive"))
      (node (ref "U24") (pin "28") (pinfunction "PGND_28") (pintype "passive"))
      (node (ref "U24") (pin "37") (pinfunction "CGND_37") (pintype "passive"))
      (node (ref "U24") (pin "41") (pinfunction "CGND_41") (pintype "passive"))
      (node (ref "U24") (pin "5") (pinfunction "CGND_5") (pintype "passive"))
    )
    (net (code "14") (name "Net-(U1-BOOT)") (class "Default")
      (node (ref "C30") (pin "1") (pinfunction "1_1") (pintype "passive"))
      (node (ref "U1") (pin "4") (pinfunction "BOOT_4") (pintype "passive"))
    )
    (net (code "15") (name "Net-(U1-DSBL#)") (class "Default")
      (node (ref "R1") (pin "1") (pinfunction "1_1") (pintype "passive"))
      (node (ref "U1") (pin "39") (pinfunction "DSBL#_39") (pintype "passive"))
    )
    (net (code "16") (name "Net-(U1-GH)") (class "Default")
      (node (ref "TP8") (pin "1") (pinfunction "1_1") (pintype "passive"))
      (node (ref "U1") (pin "6") (pinfunction "GH_6") (pintype "passive"))
    )
    (net (code "17") (name "Net-(U1-GL)") (class "Default")
      (node (ref "TP15") (pin "1") (pinfunction "1_1") (pintype "passive"))
      (node (ref "U1") (pin "36") (pinfunction "GL_36") (pintype "passive"))
    )
    (net (code "18") (name "Net-(U1-PHASE)") (class "Default")
      (node (ref "C30") (pin "2") (pinfunction "2_2") (pintype "passive"))
      (node (ref "U1") (pin "7") (pinfunction "PHASE_7") (pintype "passive"))
    )
    (net (code "19") (name "Net-(U1-VCIN)") (class "Default")
      (node (ref "C26") (pin "1") (pinfunction "1_1") (pintype "passive"))
      (node (ref "R4") (pin "2") (pinfunction "2_2") (pintype "passive"))
      (node (ref "U1") (pin "2") (pinfunction "VCIN_2") (pintype "passive"))
    )
    (net (code "20") (name "Net-(U17-BOOT)") (class "Default")
      (node (ref "C257") (pin "1") (pinfunction "1_1") (pintype "passive"))
      (node (ref "U17") (pin "4") (pinfunction "BOOT_4") (pintype "passive"))
    )
    (net (code "21") (name "Net-(U17-DSBL#)") (class "Default")
      (node (ref "R23") (pin "1") (pinfunction "1_1") (pintype "passive"))
      (node (ref "U17") (pin "39") (pinfunction "DSBL#_39") (pintype "passive"))
    )
    (net (code "22") (name "Net-(U17-GH)") (class "Default")
      (node (ref "TP31") (pin "1") (pinfunction "1_1") (pintype "passive"))
      (node (ref "U17") (pin "6") (pinfunction "GH_6") (pintype "passive"))
    )
    (net (code "23") (name "Net-(U17-GL)") (class "Default")
      (node (ref "TP27") (pin "1") (pinfunction "1_1") (pintype "passive"))
      (node (ref "U17") (pin "36") (pinfunction "GL_36") (pintype "passive"))
    )
    (net (code "24") (name "Net-(U17-PHASE)") (class "Default")
      (node (ref "C257") (pin "2") (pinfunction "2_2") (pintype "passive"))
      (node (ref "U17") (pin "7") (pinfunction "PHASE_7") (pintype "passive"))
    )
    (net (code "25") (name "Net-(U17-VCIN)") (class "Default")
      (node (ref "C58") (pin "1") (pinfunction "1_1") (pintype "passive"))
      (node (ref "R24") (pin "2") (pinfunction "2_2") (pintype "passive"))
      (node (ref "U17") (pin "2") (pinfunction "VCIN_2") (pintype "passive"))
    )
    (net (code "26") (name "Net-(U20-BOOT)") (class "Default")
      (node (ref "C93") (pin "1") (pinfunction "1_1") (pintype "passive"))
      (node (ref "U20") (pin "4") (pinfunction "BOOT_4") (pintype "passive"))
    )
    (net (code "27") (name "Net-(U20-DSBL#)") (class "Default")
      (node (ref "R2") (pin "1") (pinfunction "1_1") (pintype "passive"))
      (node (ref "U20") (pin "39") (pinfunction "DSBL#_39") (pintype "passive"))
    )
    (net (code "28") (name "Net-(U20-GH)") (class "Default")
      (node (ref "TP4") (pin "1") (pinfunction "1_1") (pintype "passive"))
      (node (ref "U20") (pin "6") (pinfunction "GH_6") (pintype "passive"))
    )
    (net (code "29") (name "Net-(U20-GL)") (class "Default")
      (node (ref "TP30") (pin "1") (pinfunction "1_1") (pintype "passive"))
      (node (ref "U20") (pin "36") (pinfunction "GL_36") (pintype "passive"))
    )
    (net (code "30") (name "Net-(U20-PHASE)") (class "Default")
      (node (ref "C93") (pin "2") (pinfunction "2_2") (pintype "passive"))
      (node (ref "U20") (pin "7") (pinfunction "PHASE_7") (pintype "passive"))
    )
    (net (code "31") (name "Net-(U20-VCIN)") (class "Default")
      (node (ref "C89") (pin "1") (pinfunction "1_1") (pintype "passive"))
      (node (ref "R3") (pin "2") (pinfunction "2_2") (pintype "passive"))
      (node (ref "U20") (pin "2") (pinfunction "VCIN_2") (pintype "passive"))
    )
    (net (code "32") (name "Net-(U24-BOOT)") (class "Default")
      (node (ref "C125") (pin "1") (pinfunction "1_1") (pintype "passive"))
      (node (ref "U24") (pin "4") (pinfunction "BOOT_4") (pintype "passive"))
    )
    (net (code "33") (name "Net-(U24-DSBL#)") (class "Default")
      (node (ref "R5") (pin "1") (pinfunction "1_1") (pintype "passive"))
      (node (ref "U24") (pin "39") (pinfunction "DSBL#_39") (pintype "passive"))
    )
    (net (code "34") (name "Net-(U24-GH)") (class "Default")
      (node (ref "TP16") (pin "1") (pinfunction "1_1") (pintype "passive"))
      (node (ref "U24") (pin "6") (pinfunction "GH_6") (pintype "passive"))
    )
    (net (code "35") (name "Net-(U24-GL)") (class "Default")
      (node (ref "TP32") (pin "1") (pinfunction "1_1") (pintype "passive"))
      (node (ref "U24") (pin "36") (pinfunction "GL_36") (pintype "passive"))
    )
    (net (code "36") (name "Net-(U24-PHASE)") (class "Default")
      (node (ref "C125") (pin "2") (pinfunction "2_2") (pintype "passive"))
      (node (ref "U24") (pin "7") (pinfunction "PHASE_7") (pintype "passive"))
    )
    (net (code "37") (name "Net-(U24-VCIN)") (class "Default")
      (node (ref "C121") (pin "1") (pinfunction "1_1") (pintype "passive"))
      (node (ref "R7") (pin "2") (pinfunction "2_2") (pintype "passive"))
      (node (ref "U24") (pin "2") (pinfunction "VCIN_2") (pintype "passive"))
    )
    (net (code "38") (name "unconnected-(U1-SMOD#-Pad1)") (class "Default")
      (node (ref "U1") (pin "1") (pinfunction "SMOD#_1") (pintype "passive+no_connect"))
    )
    (net (code "39") (name "unconnected-(U17-SMOD#-Pad1)") (class "Default")
      (node (ref "U17") (pin "1") (pinfunction "SMOD#_1") (pintype "passive+no_connect"))
    )
    (net (code "40") (name "unconnected-(U20-SMOD#-Pad1)") (class "Default")
      (node (ref "U20") (pin "1") (pinfunction "SMOD#_1") (pintype "passive+no_connect"))
    )
    (net (code "41") (name "unconnected-(U24-SMOD#-Pad1)") (class "Default")
      (node (ref "U24") (pin "1") (pinfunction "SMOD#_1") (pintype "passive+no_connect"))
    )
  )
)
